# pocketbone.net
KiCad netlist of a schematic drawn in EAGLE
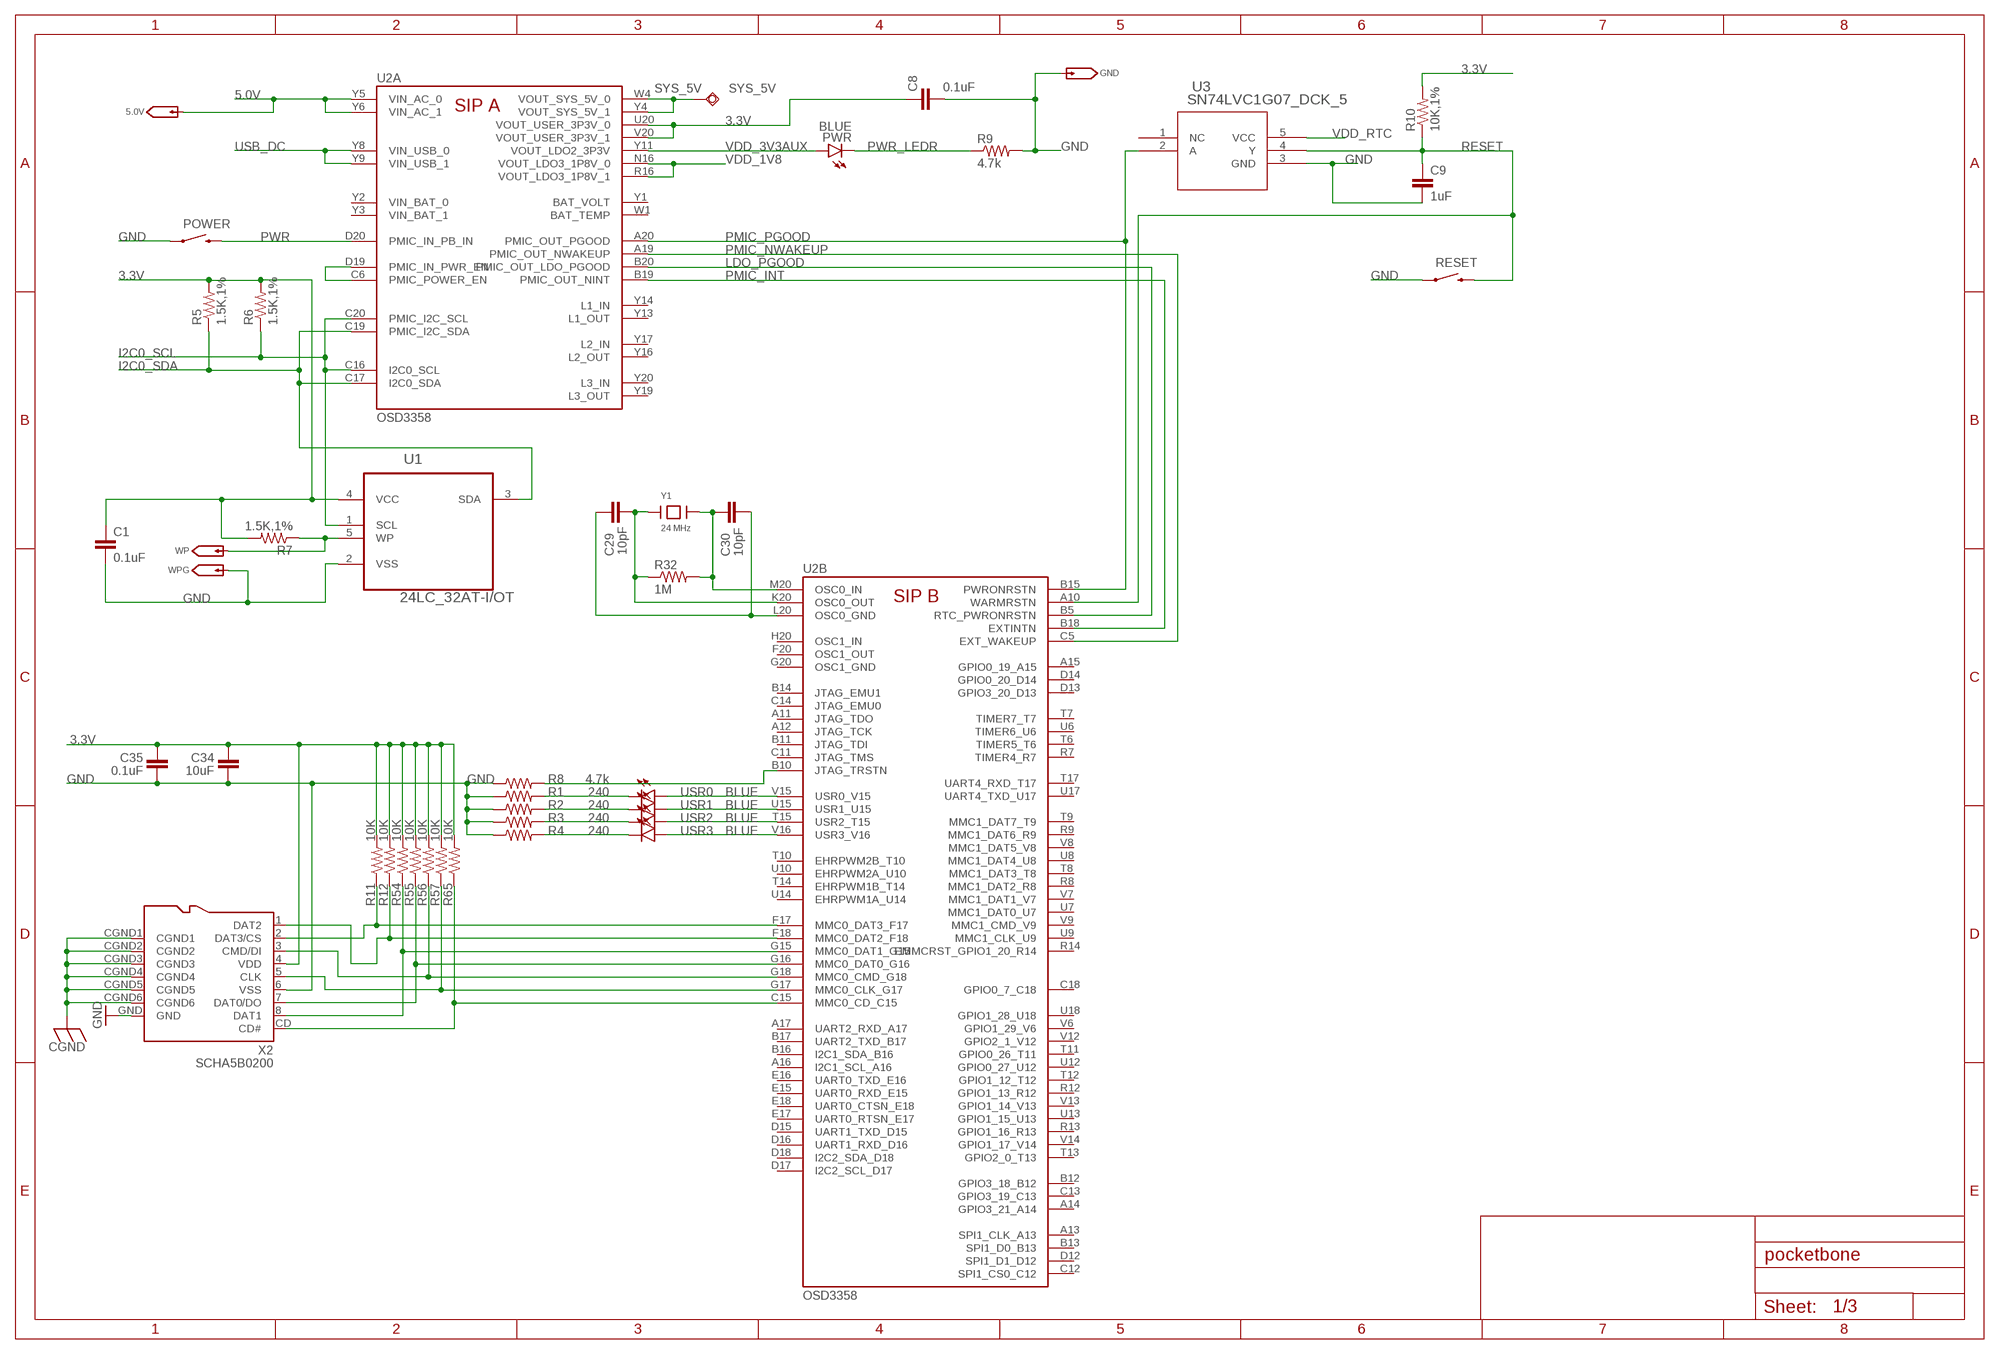
[diagram p0: schematic, sheet 1]
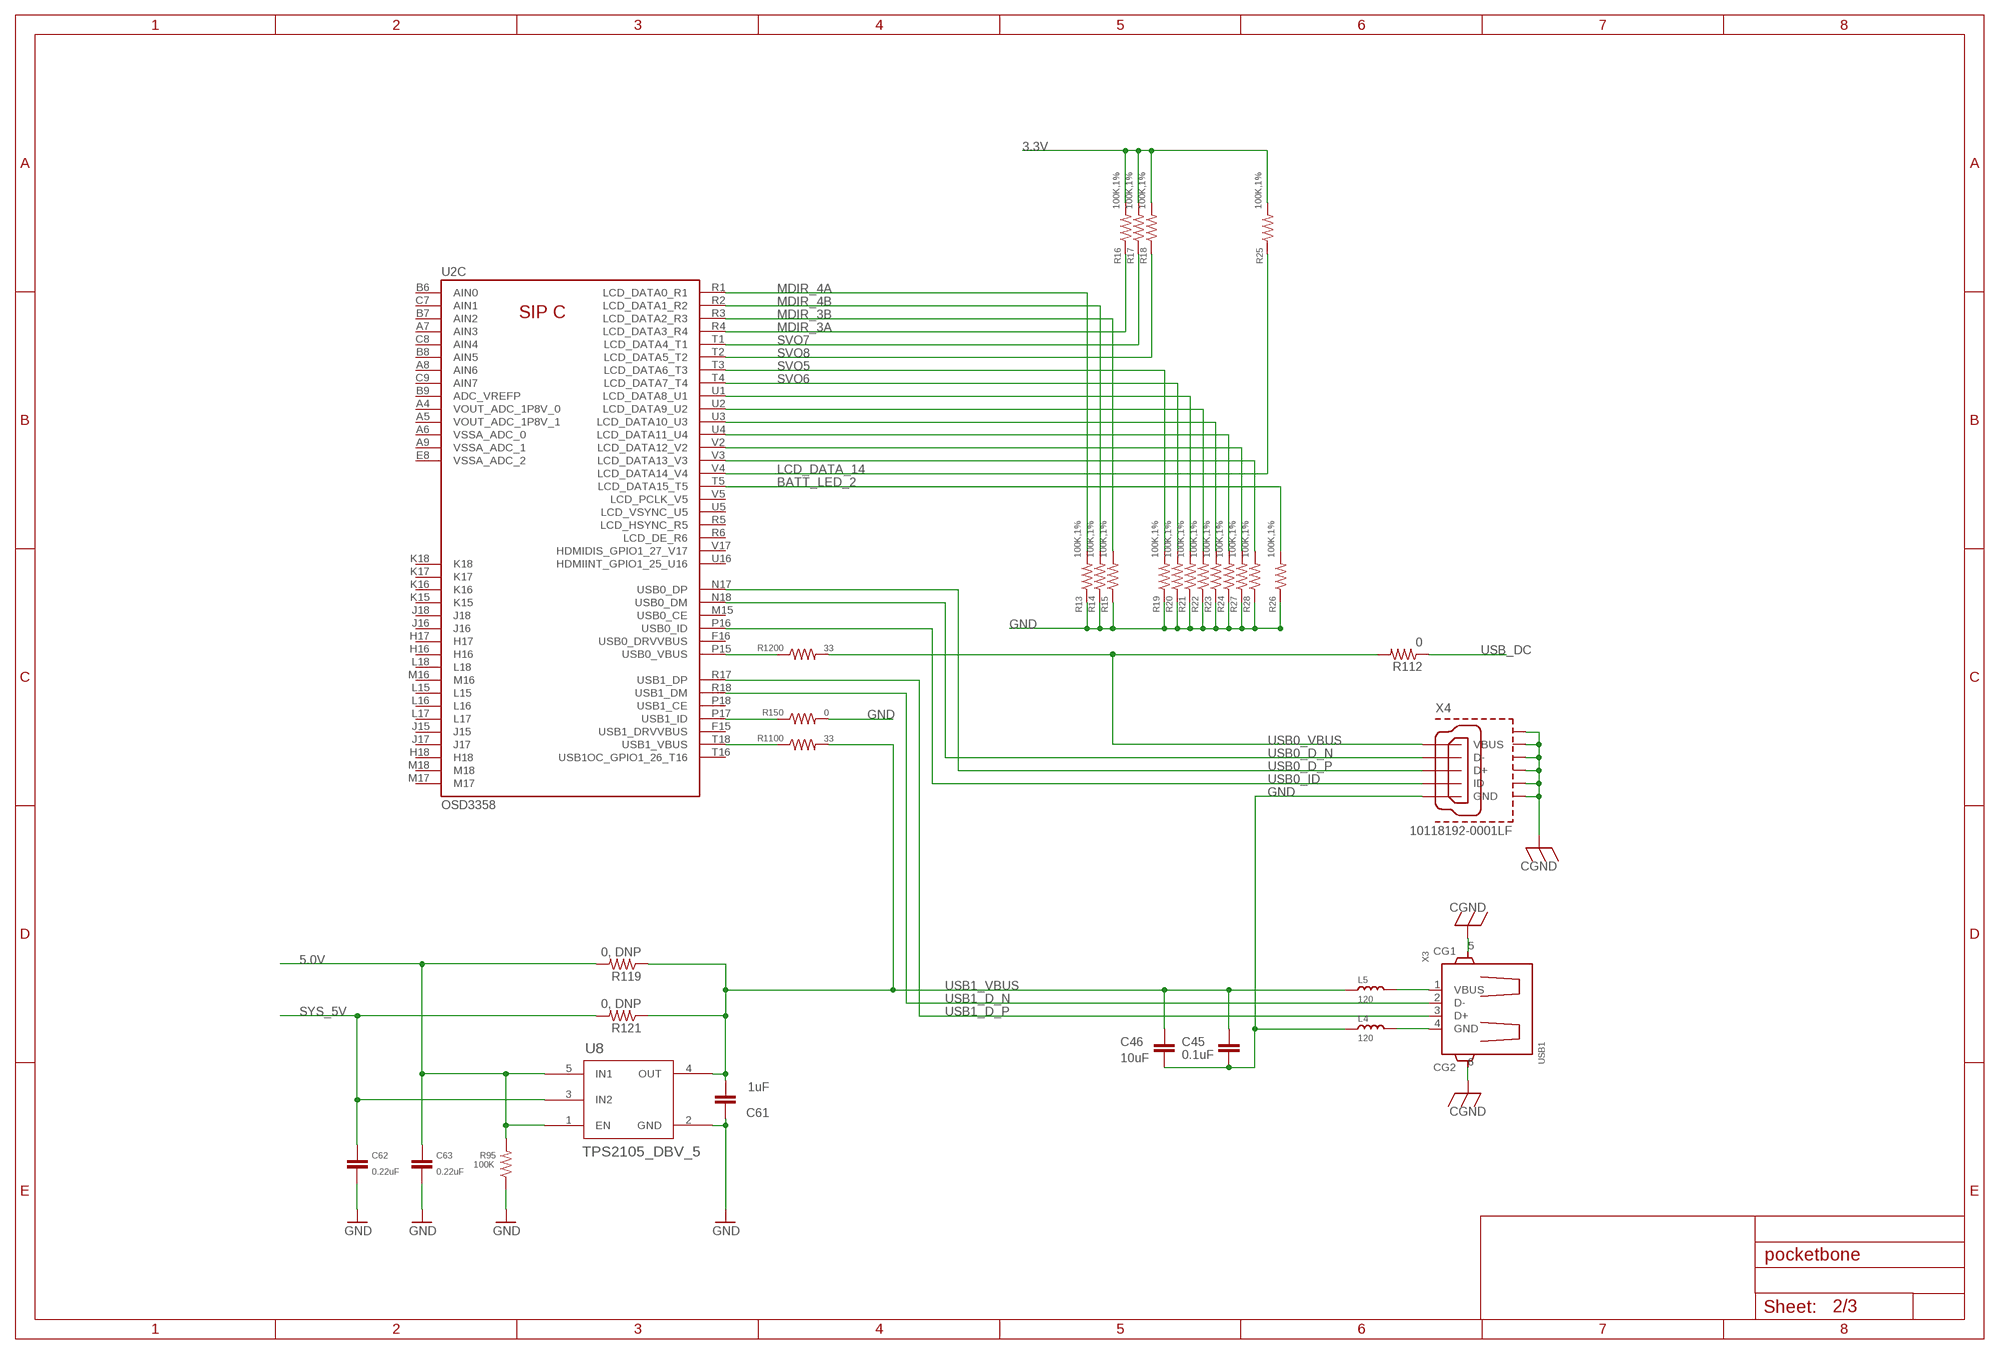
[diagram p1: schematic, sheet 2]
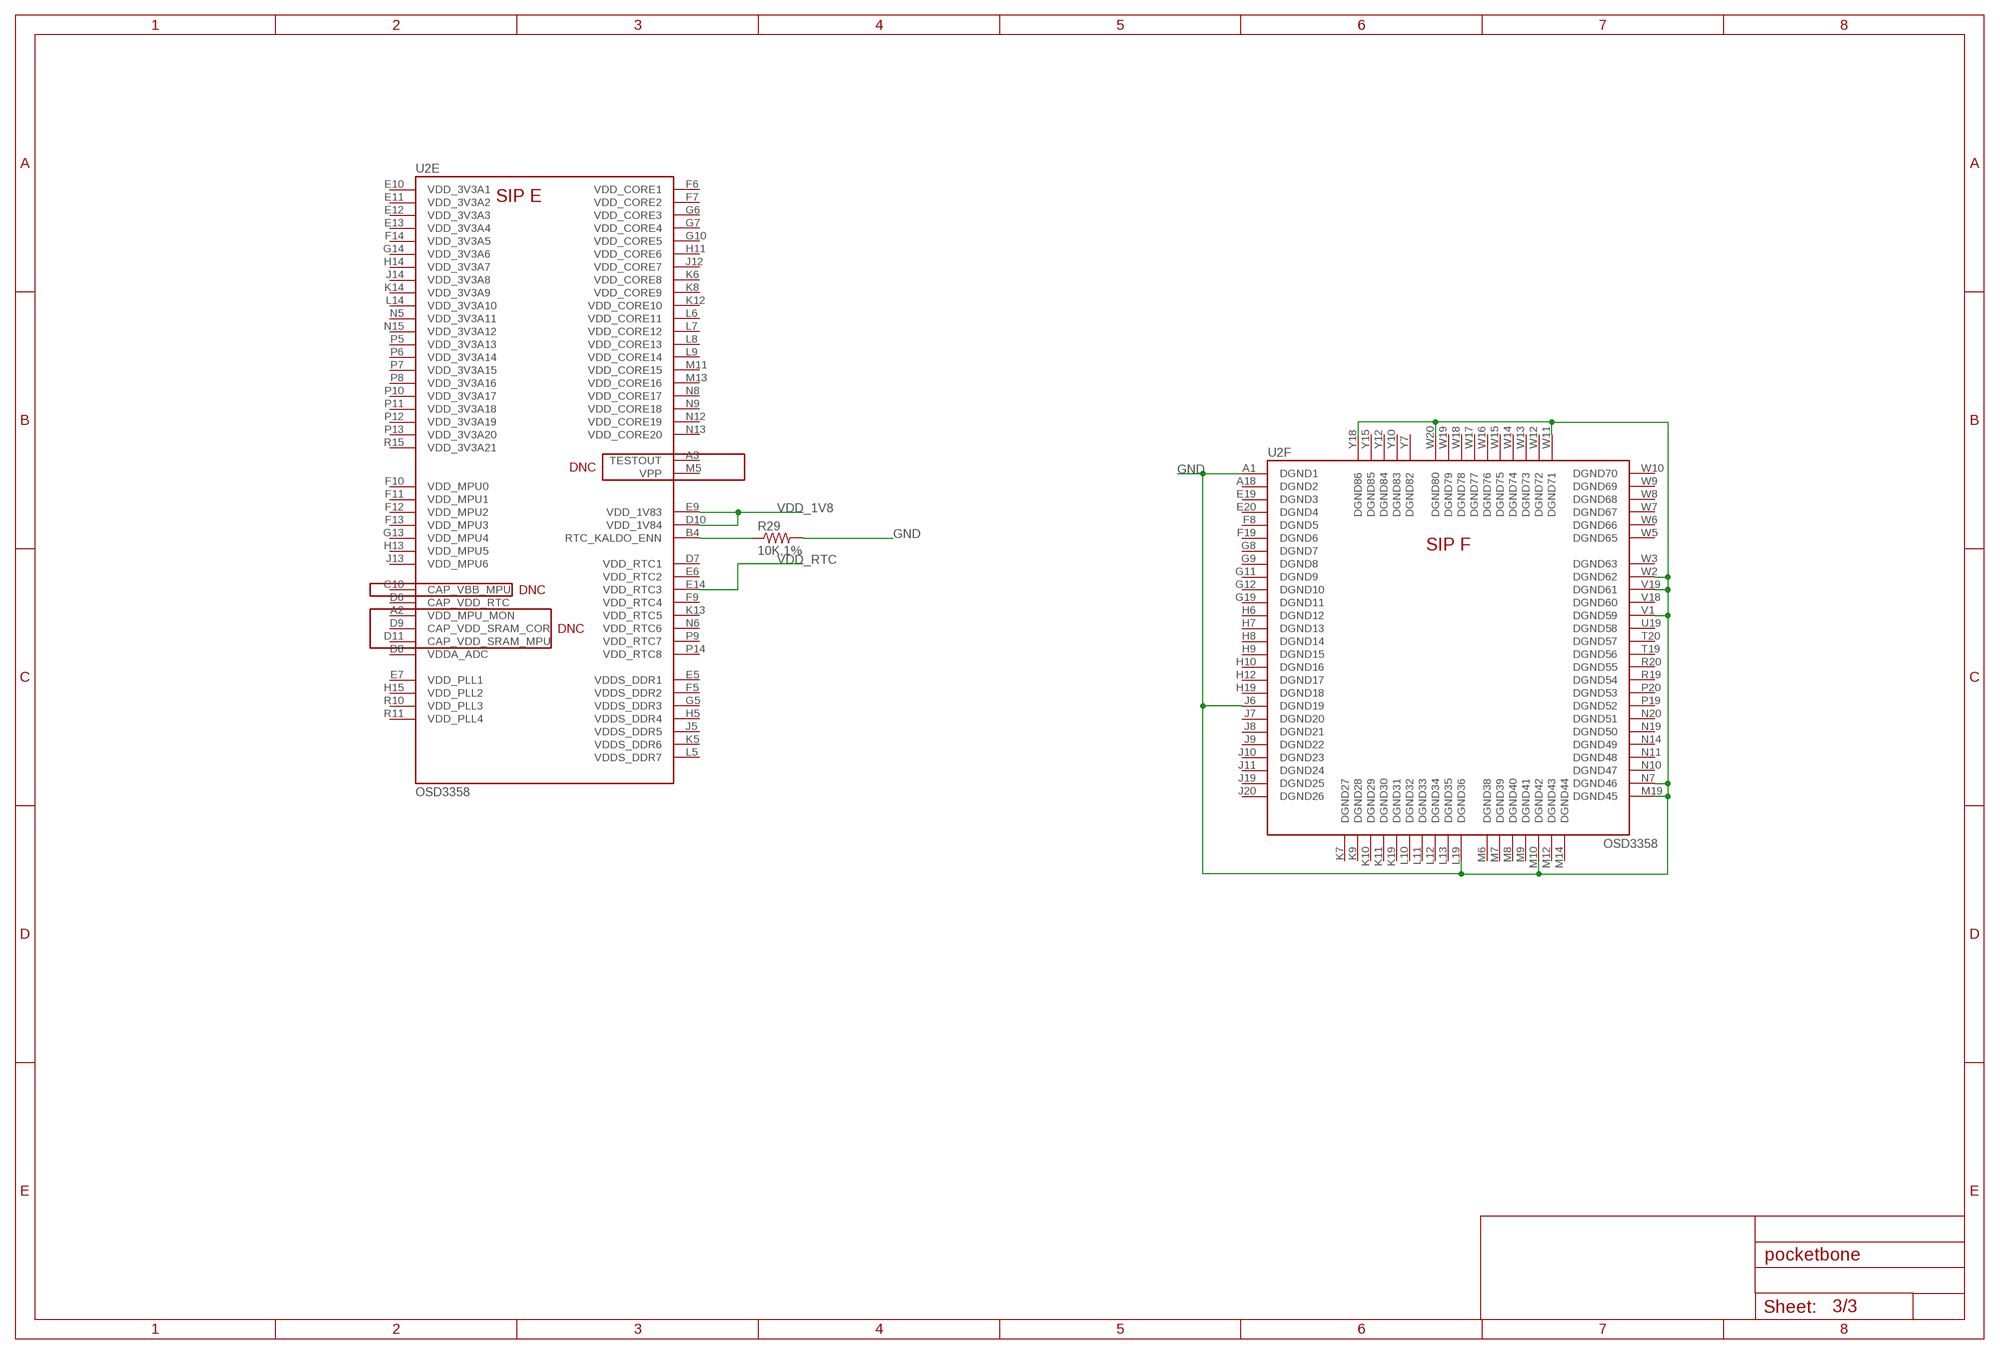
[diagram p2: schematic, sheet 3]

(export (version "E")
  (design (tool "Eeschema 10.0.6"))
  (components
    (comp (ref "C45")
      (value "0.1uF")
      (footprint "eagle-import:0402-CAP")
      (libsource (lib "eagle-import") (part "CAP0402-CAP"))
    )
    (comp (ref "C46")
      (value "10uF")
      (footprint "eagle-import:0805")
      (libsource (lib "eagle-import") (part "CAP0805"))
    )
    (comp (ref "C61")
      (value "1uF")
      (footprint "eagle-import:0402-CAP")
      (libsource (lib "eagle-import") (part "CAP0402-CAP"))
    )
    (comp (ref "C62")
      (value "0.22uF")
      (footprint "eagle-import:0402-CAP")
      (libsource (lib "eagle-import") (part "CAP0402-CAP"))
    )
    (comp (ref "C63")
      (value "0.22uF")
      (footprint "eagle-import:0402-CAP")
      (libsource (lib "eagle-import") (part "CAP0402-CAP"))
    )
    (comp (ref "L4")
      (value "120")
      (footprint "eagle-import:L0603")
      (libsource (lib "eagle-import") (part "INDUCTOR/FERRITE-BEAD'0603'"))
    )
    (comp (ref "L5")
      (value "120")
      (footprint "eagle-import:L0603")
      (libsource (lib "eagle-import") (part "INDUCTOR/FERRITE-BEAD'0603'"))
    )
    (comp (ref "R13")
      (value "100K,1%")
      (footprint "eagle-import:0402-RES")
      (libsource (lib "eagle-import") (part "RESISTOR0402-RES"))
    )
    (comp (ref "R14")
      (value "100K,1%")
      (footprint "eagle-import:0402-RES")
      (libsource (lib "eagle-import") (part "RESISTOR0402-RES"))
    )
    (comp (ref "R15")
      (value "100K,1%")
      (footprint "eagle-import:0402-RES")
      (libsource (lib "eagle-import") (part "RESISTOR0402-RES"))
    )
    (comp (ref "R16")
      (value "100K,1%")
      (footprint "eagle-import:0402-RES")
      (libsource (lib "eagle-import") (part "RESISTOR0402-RES"))
    )
    (comp (ref "R17")
      (value "100K,1%")
      (footprint "eagle-import:0402-RES")
      (libsource (lib "eagle-import") (part "RESISTOR0402-RES"))
    )
    (comp (ref "R18")
      (value "100K,1%")
      (footprint "eagle-import:0402-RES")
      (libsource (lib "eagle-import") (part "RESISTOR0402-RES"))
    )
    (comp (ref "R19")
      (value "100K,1%")
      (footprint "eagle-import:0402-RES")
      (libsource (lib "eagle-import") (part "RESISTOR0402-RES"))
    )
    (comp (ref "R20")
      (value "100K,1%")
      (footprint "eagle-import:0402-RES")
      (libsource (lib "eagle-import") (part "RESISTOR0402-RES"))
    )
    (comp (ref "R21")
      (value "100K,1%")
      (footprint "eagle-import:0402-RES")
      (libsource (lib "eagle-import") (part "RESISTOR0402-RES"))
    )
    (comp (ref "R22")
      (value "100K,1%")
      (footprint "eagle-import:0402-RES")
      (libsource (lib "eagle-import") (part "RESISTOR0402-RES"))
    )
    (comp (ref "R23")
      (value "100K,1%")
      (footprint "eagle-import:0402-RES")
      (libsource (lib "eagle-import") (part "RESISTOR0402-RES"))
    )
    (comp (ref "R24")
      (value "100K,1%")
      (footprint "eagle-import:0402-RES")
      (libsource (lib "eagle-import") (part "RESISTOR0402-RES"))
    )
    (comp (ref "R25")
      (value "100K,1%")
      (footprint "eagle-import:0402-RES")
      (libsource (lib "eagle-import") (part "RESISTOR0402-RES"))
    )
    (comp (ref "R26")
      (value "100K,1%")
      (footprint "eagle-import:0402-RES")
      (libsource (lib "eagle-import") (part "RESISTOR0402-RES"))
    )
    (comp (ref "R27")
      (value "100K,1%")
      (footprint "eagle-import:0402-RES")
      (libsource (lib "eagle-import") (part "RESISTOR0402-RES"))
    )
    (comp (ref "R28")
      (value "100K,1%")
      (footprint "eagle-import:0402-RES")
      (libsource (lib "eagle-import") (part "RESISTOR0402-RES"))
    )
    (comp (ref "R95")
      (value "100K")
      (footprint "eagle-import:0402-RES")
      (libsource (lib "eagle-import") (part "RESISTOR0402-RES"))
    )
    (comp (ref "R112")
      (value "0")
      (footprint "eagle-import:0603-RES")
      (libsource (lib "eagle-import") (part "RESISTOR0603"))
    )
    (comp (ref "R119")
      (value "0, DNP")
      (footprint "eagle-import:0603-RES")
      (libsource (lib "eagle-import") (part "RESISTOR0603"))
    )
    (comp (ref "R121")
      (value "0, DNP")
      (footprint "eagle-import:0603-RES")
      (libsource (lib "eagle-import") (part "RESISTOR0603"))
    )
    (comp (ref "R150")
      (value "0")
      (footprint "eagle-import:0402-RES")
      (libsource (lib "eagle-import") (part "RESISTOR0402-RES"))
    )
    (comp (ref "R1100")
      (value "33")
      (footprint "eagle-import:0402-RES")
      (libsource (lib "eagle-import") (part "RESISTOR0402-RES"))
    )
    (comp (ref "R1200")
      (value "33")
      (footprint "eagle-import:0402-RES")
      (libsource (lib "eagle-import") (part "RESISTOR0402-RES"))
    )
    (comp (ref "U2")
      (value "OSD3358")
      (footprint "eagle-import:OSD3358")
      (libsource (lib "eagle-import") (part "OSD3358"))
    )
    (comp (ref "U8")
      (value "TPS2105_DBV_5")
      (footprint "eagle-import:DBV5")
      (fields
        (field (name "GENERIC_PART_NUMBER") "TPS2105")
        (field (name "MANUFACTURER") "Texas Instruments")
        (field (name "MANUFACTURER_PART_NUMBER") "tps2105_dbv_5")
      )
      (libsource (lib "eagle-import") (part "TPS2105_DBV_5"))
    )
    (comp (ref "X3")
      (value "USB1")
      (footprint "eagle-import:USB_HOST_HORIZONTAL_W_CHASSIS_GND")
      (libsource (lib "eagle-import") (part "USB_HOST_W/CHASSIS_GND"))
    )
    (comp (ref "X4")
      (value "10118192-0001LF")
      (footprint "eagle-import:10118192-0001LF(MICRO-USB-B-AMPHENOL-FCI)")
      (libsource (lib "eagle-import") (part "10118192-0001LF"))
    )
    (comp (ref "5.0V")
      (value "GHI_TESTPAD/W_HOLE_1X1")
      (footprint "eagle-import:GHI2_TESTPAD_W_HOLE_1X1")
      (libsource (lib "eagle-import") (part "GHI_TESTPAD/W_HOLE_1X1"))
    )
    (comp (ref "C1")
      (value "0.1uF")
      (footprint "eagle-import:0402-CAP")
      (libsource (lib "eagle-import") (part "CAP0402-CAP"))
    )
    (comp (ref "C8")
      (value "0.1uF")
      (footprint "eagle-import:0402-CAP")
      (libsource (lib "eagle-import") (part "CAP0402-CAP"))
    )
    (comp (ref "C9")
      (value "1uF")
      (footprint "eagle-import:0402-CAP")
      (libsource (lib "eagle-import") (part "CAP0402-CAP"))
    )
    (comp (ref "C29")
      (value "10pF")
      (footprint "eagle-import:0402-CAP")
      (libsource (lib "eagle-import") (part "CAP0402-CAP"))
    )
    (comp (ref "C30")
      (value "10pF")
      (footprint "eagle-import:0402-CAP")
      (libsource (lib "eagle-import") (part "CAP0402-CAP"))
    )
    (comp (ref "C34")
      (value "10uF")
      (footprint "eagle-import:0805")
      (libsource (lib "eagle-import") (part "CAP0805"))
    )
    (comp (ref "C35")
      (value "0.1uF")
      (footprint "eagle-import:0402-CAP")
      (libsource (lib "eagle-import") (part "CAP0402-CAP"))
    )
    (comp (ref "GND")
      (value "GHI_TESTPAD/W_HOLE_1X1")
      (footprint "eagle-import:GHI2_TESTPAD_W_HOLE_1X1")
      (libsource (lib "eagle-import") (part "GHI_TESTPAD/W_HOLE_1X1"))
    )
    (comp (ref "POWER")
      (value "SWITCH-MOMENTARY-2SMD-1101NE")
      (footprint "eagle-import:TACTILE-SWITCH-1101NE")
      (libsource (lib "eagle-import") (part "SWITCH-MOMENTARY-2SMD-1101NE"))
    )
    (comp (ref "PWR")
      (value "BLUE")
      (footprint "eagle-import:LED-0603")
      (libsource (lib "eagle-import") (part "LED0603"))
    )
    (comp (ref "R1")
      (value "240")
      (footprint "eagle-import:0402-RES")
      (libsource (lib "eagle-import") (part "RESISTOR0402-RES"))
    )
    (comp (ref "R2")
      (value "240")
      (footprint "eagle-import:0402-RES")
      (libsource (lib "eagle-import") (part "RESISTOR0402-RES"))
    )
    (comp (ref "R3")
      (value "240")
      (footprint "eagle-import:0402-RES")
      (libsource (lib "eagle-import") (part "RESISTOR0402-RES"))
    )
    (comp (ref "R4")
      (value "240")
      (footprint "eagle-import:0402-RES")
      (libsource (lib "eagle-import") (part "RESISTOR0402-RES"))
    )
    (comp (ref "R5")
      (value "1.5K,1%")
      (footprint "eagle-import:0402-RES")
      (libsource (lib "eagle-import") (part "RESISTOR0402-RES"))
    )
    (comp (ref "R6")
      (value "1.5K,1%")
      (footprint "eagle-import:0402-RES")
      (libsource (lib "eagle-import") (part "RESISTOR0402-RES"))
    )
    (comp (ref "R7")
      (value "1.5K,1%")
      (footprint "eagle-import:0402-RES")
      (libsource (lib "eagle-import") (part "RESISTOR0402-RES"))
    )
    (comp (ref "R8")
      (value "4.7k")
      (footprint "eagle-import:0402-RES")
      (libsource (lib "eagle-import") (part "RESISTOR0402-RES"))
    )
    (comp (ref "R9")
      (value "4.7k")
      (footprint "eagle-import:0402-RES")
      (libsource (lib "eagle-import") (part "RESISTOR0402-RES"))
    )
    (comp (ref "R10")
      (value "10K,1%")
      (footprint "eagle-import:0402-RES")
      (libsource (lib "eagle-import") (part "RESISTOR0402-RES"))
    )
    (comp (ref "R11")
      (value "10K")
      (footprint "eagle-import:0402-RES")
      (libsource (lib "eagle-import") (part "RESISTOR0402-RES"))
    )
    (comp (ref "R12")
      (value "10K")
      (footprint "eagle-import:0402-RES")
      (libsource (lib "eagle-import") (part "RESISTOR0402-RES"))
    )
    (comp (ref "R32")
      (value "1M")
      (footprint "eagle-import:0402-RES")
      (libsource (lib "eagle-import") (part "RESISTOR0402-RES"))
    )
    (comp (ref "R54")
      (value "10K")
      (footprint "eagle-import:0402-RES")
      (libsource (lib "eagle-import") (part "RESISTOR0402-RES"))
    )
    (comp (ref "R55")
      (value "10K")
      (footprint "eagle-import:0402-RES")
      (libsource (lib "eagle-import") (part "RESISTOR0402-RES"))
    )
    (comp (ref "R56")
      (value "10K")
      (footprint "eagle-import:0402-RES")
      (libsource (lib "eagle-import") (part "RESISTOR0402-RES"))
    )
    (comp (ref "R57")
      (value "10K")
      (footprint "eagle-import:0402-RES")
      (libsource (lib "eagle-import") (part "RESISTOR0402-RES"))
    )
    (comp (ref "R65")
      (value "10K")
      (footprint "eagle-import:0402-RES")
      (libsource (lib "eagle-import") (part "RESISTOR0402-RES"))
    )
    (comp (ref "RESET")
      (value "SWITCH-MOMENTARY-2SMD-1101NE")
      (footprint "eagle-import:TACTILE-SWITCH-1101NE")
      (libsource (lib "eagle-import") (part "SWITCH-MOMENTARY-2SMD-1101NE"))
    )
    (comp (ref "SYS_5V")
      (value "TPSQB1,27")
      (footprint "eagle-import:B1,27")
      (libsource (lib "eagle-import") (part "TPSQB1,27"))
    )
    (comp (ref "U1")
      (value "24LC_32AT-I/OT")
      (footprint "eagle-import:SOT95P290X145-5N")
      (fields (field (name "MPN") "24LC32AT-I/OT"))
      (libsource (lib "eagle-import") (part "24LC_32AT-I/OT"))
    )
    (comp (ref "U3")
      (value "SN74LVC1G07_DCK_5")
      (footprint "eagle-import:DCK5")
      (fields
        (field (name "GENERIC_PART_NUMBER") "SN74LVC1G07")
        (field (name "MANUFACTURER") "Texas Instruments")
        (field (name "MANUFACTURER_PART_NUMBER") "sn74lvc1g07_dck_5")
      )
      (libsource (lib "eagle-import") (part "SN74LVC1G07_DCK_5"))
    )
    (comp (ref "USR0")
      (value "BLUE")
      (footprint "eagle-import:LED-0603")
      (libsource (lib "eagle-import") (part "LED0603"))
    )
    (comp (ref "USR1")
      (value "BLUE")
      (footprint "eagle-import:LED-0603")
      (libsource (lib "eagle-import") (part "LED0603"))
    )
    (comp (ref "USR2")
      (value "BLUE")
      (footprint "eagle-import:LED-0603")
      (libsource (lib "eagle-import") (part "LED0603"))
    )
    (comp (ref "USR3")
      (value "BLUE")
      (footprint "eagle-import:LED-0603")
      (libsource (lib "eagle-import") (part "LED0603"))
    )
    (comp (ref "WP")
      (value "GHI_TESTPAD/W_HOLE_1X1")
      (footprint "eagle-import:GHI2_TESTPAD_W_HOLE_1X1")
      (libsource (lib "eagle-import") (part "GHI_TESTPAD/W_HOLE_1X1"))
    )
    (comp (ref "WPG")
      (value "GHI_TESTPAD/W_HOLE_1X1")
      (footprint "eagle-import:GHI2_TESTPAD_W_HOLE_1X1")
      (libsource (lib "eagle-import") (part "GHI_TESTPAD/W_HOLE_1X1"))
    )
    (comp (ref "X2")
      (value "SCHA5B0200")
      (footprint "eagle-import:SCHA5B0200")
      (libsource (lib "eagle-import") (part "SCHA5B0200(ALPS_USD)"))
    )
    (comp (ref "Y1")
      (value "24 MHz")
      (footprint "eagle-import:CRYSTAL_5X3.2MM")
      (libsource (lib "eagle-import") (part "CRYSTAL_5X3.2MM"))
    )
    (comp (ref "R29")
      (value "10K,1%")
      (footprint "eagle-import:0402-RES")
      (libsource (lib "eagle-import") (part "RESISTOR0402-RES"))
    )
  )
  (nets
    (net (code "1") (name "3.3V") (class "Default")
      (node (ref "C1") (pin "1") (pinfunction "1_1") (pintype "passive"))
      (node (ref "C34") (pin "2") (pinfunction "2_2") (pintype "passive"))
      (node (ref "C35") (pin "2") (pinfunction "2_2") (pintype "passive"))
      (node (ref "C8") (pin "1") (pinfunction "1_1") (pintype "passive"))
      (node (ref "R10") (pin "2") (pinfunction "2_2") (pintype "passive"))
      (node (ref "R11") (pin "2") (pinfunction "2_2") (pintype "passive"))
      (node (ref "R12") (pin "2") (pinfunction "2_2") (pintype "passive"))
      (node (ref "R16") (pin "2") (pinfunction "2_2") (pintype "passive"))
      (node (ref "R17") (pin "2") (pinfunction "2_2") (pintype "passive"))
      (node (ref "R18") (pin "2") (pinfunction "2_2") (pintype "passive"))
      (node (ref "R25") (pin "2") (pinfunction "2_2") (pintype "passive"))
      (node (ref "R5") (pin "2") (pinfunction "2_2") (pintype "passive"))
      (node (ref "R54") (pin "2") (pinfunction "2_2") (pintype "passive"))
      (node (ref "R55") (pin "2") (pinfunction "2_2") (pintype "passive"))
      (node (ref "R56") (pin "2") (pinfunction "2_2") (pintype "passive"))
      (node (ref "R57") (pin "2") (pinfunction "2_2") (pintype "passive"))
      (node (ref "R6") (pin "2") (pinfunction "2_2") (pintype "passive"))
      (node (ref "R65") (pin "2") (pinfunction "2_2") (pintype "passive"))
      (node (ref "R7") (pin "2") (pinfunction "2_2") (pintype "passive"))
      (node (ref "U1") (pin "4") (pinfunction "VCC_4") (pintype "power_in"))
      (node (ref "U2") (pin "U20") (pinfunction "VOUT_USER_3P3V_0_U20") (pintype "power_in"))
      (node (ref "U2") (pin "V20") (pinfunction "VOUT_USER_3P3V_1_V20") (pintype "power_in"))
      (node (ref "X2") (pin "4") (pinfunction "VDD_4") (pintype "bidirectional"))
    )
    (net (code "2") (name "5.0V") (class "Default")
      (node (ref "5.0V") (pin "P$1") (pinfunction "TP_P$1") (pintype "bidirectional"))
      (node (ref "C63") (pin "1") (pinfunction "1_1") (pintype "passive"))
      (node (ref "R119") (pin "2") (pinfunction "2_2") (pintype "passive"))
      (node (ref "R95") (pin "2") (pinfunction "2_2") (pintype "passive"))
      (node (ref "U2") (pin "Y5") (pinfunction "VIN_AC_0_Y5") (pintype "power_in"))
      (node (ref "U2") (pin "Y6") (pinfunction "VIN_AC_1_Y6") (pintype "power_in"))
      (node (ref "U8") (pin "1") (pinfunction "EN_1") (pintype "input"))
      (node (ref "U8") (pin "5") (pinfunction "IN1_5") (pintype "input"))
    )
    (net (code "3") (name "BATT_LED_2") (class "Default")
      (node (ref "R26") (pin "2") (pinfunction "2_2") (pintype "passive"))
      (node (ref "U2") (pin "T5") (pinfunction "LCD_DATA15_T5_T5") (pintype "bidirectional"))
    )
    (net (code "4") (name "CGND") (class "Default")
      (node (ref "X2") (pin "CGND1") (pinfunction "CGND1_CGND1") (pintype "bidirectional"))
      (node (ref "X2") (pin "CGND2") (pinfunction "CGND2_CGND2") (pintype "bidirectional"))
      (node (ref "X2") (pin "CGND3") (pinfunction "CGND3_CGND3") (pintype "bidirectional"))
      (node (ref "X2") (pin "CGND4") (pinfunction "CGND4_CGND4") (pintype "bidirectional"))
      (node (ref "X2") (pin "CGND5") (pinfunction "CGND5_CGND5") (pintype "bidirectional"))
      (node (ref "X2") (pin "CGND6") (pinfunction "CGND6_CGND6") (pintype "bidirectional"))
      (node (ref "X3") (pin "5") (pinfunction "CG1_5") (pintype "bidirectional"))
      (node (ref "X3") (pin "6") (pinfunction "CG2_6") (pintype "bidirectional"))
      (node (ref "X4") (pin "CGND1") (pinfunction "SGND1_CGND1") (pintype "bidirectional"))
      (node (ref "X4") (pin "CGND2") (pinfunction "SGND2_CGND2") (pintype "bidirectional"))
      (node (ref "X4") (pin "CGND3") (pinfunction "SGND3_CGND3") (pintype "bidirectional"))
      (node (ref "X4") (pin "CGND4") (pinfunction "SGND4_CGND4") (pintype "bidirectional"))
      (node (ref "X4") (pin "CGND5") (pinfunction "SGND5_CGND5") (pintype "bidirectional"))
      (node (ref "X4") (pin "CGND6") (pinfunction "SGND6_CGND6") (pintype "bidirectional"))
    )
    (net (code "5") (name "GND") (class "Default")
      (node (ref "C1") (pin "2") (pinfunction "2_2") (pintype "passive"))
      (node (ref "C34") (pin "1") (pinfunction "1_1") (pintype "passive"))
      (node (ref "C35") (pin "1") (pinfunction "1_1") (pintype "passive"))
      (node (ref "C45") (pin "2") (pinfunction "2_2") (pintype "passive"))
      (node (ref "C46") (pin "2") (pinfunction "2_2") (pintype "passive"))
      (node (ref "C61") (pin "1") (pinfunction "1_1") (pintype "passive"))
      (node (ref "C62") (pin "2") (pinfunction "2_2") (pintype "passive"))
      (node (ref "C63") (pin "2") (pinfunction "2_2") (pintype "passive"))
      (node (ref "C8") (pin "2") (pinfunction "2_2") (pintype "passive"))
      (node (ref "C9") (pin "2") (pinfunction "2_2") (pintype "passive"))
      (node (ref "GND") (pin "P$1") (pinfunction "TP_P$1") (pintype "bidirectional"))
      (node (ref "L4") (pin "1") (pinfunction "1_1") (pintype "passive"))
      (node (ref "POWER") (pin "1") (pinfunction "1_1") (pintype "passive"))
      (node (ref "R1") (pin "1") (pinfunction "1_1") (pintype "passive"))
      (node (ref "R13") (pin "1") (pinfunction "1_1") (pintype "passive"))
      (node (ref "R14") (pin "1") (pinfunction "1_1") (pintype "passive"))
      (node (ref "R15") (pin "1") (pinfunction "1_1") (pintype "passive"))
      (node (ref "R150") (pin "2") (pinfunction "2_2") (pintype "passive"))
      (node (ref "R19") (pin "1") (pinfunction "1_1") (pintype "passive"))
      (node (ref "R2") (pin "1") (pinfunction "1_1") (pintype "passive"))
      (node (ref "R20") (pin "1") (pinfunction "1_1") (pintype "passive"))
      (node (ref "R21") (pin "1") (pinfunction "1_1") (pintype "passive"))
      (node (ref "R22") (pin "1") (pinfunction "1_1") (pintype "passive"))
      (node (ref "R23") (pin "1") (pinfunction "1_1") (pintype "passive"))
      (node (ref "R24") (pin "1") (pinfunction "1_1") (pintype "passive"))
      (node (ref "R26") (pin "1") (pinfunction "1_1") (pintype "passive"))
      (node (ref "R27") (pin "1") (pinfunction "1_1") (pintype "passive"))
      (node (ref "R28") (pin "1") (pinfunction "1_1") (pintype "passive"))
      (node (ref "R29") (pin "2") (pinfunction "2_2") (pintype "passive"))
      (node (ref "R3") (pin "1") (pinfunction "1_1") (pintype "passive"))
      (node (ref "R4") (pin "1") (pinfunction "1_1") (pintype "passive"))
      (node (ref "R8") (pin "1") (pinfunction "1_1") (pintype "passive"))
      (node (ref "R9") (pin "2") (pinfunction "2_2") (pintype "passive"))
      (node (ref "R95") (pin "1") (pinfunction "1_1") (pintype "passive"))
      (node (ref "RESET") (pin "1") (pinfunction "1_1") (pintype "passive"))
      (node (ref "U1") (pin "2") (pinfunction "VSS_2") (pintype "passive"))
      (node (ref "U2") (pin "A1") (pinfunction "DGND1_A1") (pintype "bidirectional"))
      (node (ref "U2") (pin "J6") (pinfunction "DGND19_J6") (pintype "bidirectional"))
      (node (ref "U2") (pin "L19") (pinfunction "DGND36_L19") (pintype "bidirectional"))
      (node (ref "U2") (pin "M10") (pinfunction "DGND42_M10") (pintype "bidirectional"))
      (node (ref "U2") (pin "M19") (pinfunction "DGND45_M19") (pintype "bidirectional"))
      (node (ref "U2") (pin "N7") (pinfunction "DGND46_N7") (pintype "bidirectional"))
      (node (ref "U2") (pin "V1") (pinfunction "DGND59_V1") (pintype "bidirectional"))
      (node (ref "U2") (pin "V19") (pinfunction "DGND61_V19") (pintype "bidirectional"))
      (node (ref "U2") (pin "W11") (pinfunction "DGND71_W11") (pintype "bidirectional"))
      (node (ref "U2") (pin "W2") (pinfunction "DGND62_W2") (pintype "bidirectional"))
      (node (ref "U2") (pin "W20") (pinfunction "DGND80_W20") (pintype "bidirectional"))
      (node (ref "U2") (pin "Y18") (pinfunction "DGND86_Y18") (pintype "bidirectional"))
      (node (ref "U3") (pin "3") (pinfunction "GND_3") (pintype "power_in"))
      (node (ref "U8") (pin "2") (pinfunction "GND_2") (pintype "power_in"))
      (node (ref "WPG") (pin "P$1") (pinfunction "TP_P$1") (pintype "bidirectional"))
      (node (ref "X2") (pin "6") (pinfunction "VSS_6") (pintype "bidirectional"))
      (node (ref "X2") (pin "GND") (pinfunction "GND_GND") (pintype "bidirectional"))
      (node (ref "X4") (pin "GND") (pinfunction "GND_GND") (pintype "input"))
    )
    (net (code "6") (name "I2C0_SCL") (class "Default")
      (node (ref "R6") (pin "1") (pinfunction "1_1") (pintype "passive"))
      (node (ref "U1") (pin "1") (pinfunction "SCL_1") (pintype "input"))
      (node (ref "U2") (pin "C16") (pinfunction "I2C0_SCL_C16") (pintype "bidirectional"))
      (node (ref "U2") (pin "C20") (pinfunction "PMIC_I2C_SCL_C20") (pintype "bidirectional"))
    )
    (net (code "7") (name "I2C0_SDA") (class "Default")
      (node (ref "R5") (pin "1") (pinfunction "1_1") (pintype "passive"))
      (node (ref "U1") (pin "3") (pinfunction "SDA_3") (pintype "bidirectional"))
      (node (ref "U2") (pin "C17") (pinfunction "I2C0_SDA_C17") (pintype "bidirectional"))
      (node (ref "U2") (pin "C19") (pinfunction "PMIC_I2C_SDA_C19") (pintype "bidirectional"))
    )
    (net (code "8") (name "LCD_DATA_14") (class "Default")
      (node (ref "R25") (pin "1") (pinfunction "1_1") (pintype "passive"))
      (node (ref "U2") (pin "V4") (pinfunction "LCD_DATA14_V4_V4") (pintype "bidirectional"))
    )
    (net (code "9") (name "LDO_PGOOD") (class "Default")
      (node (ref "U2") (pin "B20") (pinfunction "PMIC_OUT_LDO_PGOOD_B20") (pintype "output"))
      (node (ref "U2") (pin "B5") (pinfunction "RTC_PWRONRSTN_B5") (pintype "bidirectional"))
    )
    (net (code "10") (name "MDIR_3A") (class "Default")
      (node (ref "R16") (pin "1") (pinfunction "1_1") (pintype "passive"))
      (node (ref "U2") (pin "R4") (pinfunction "LCD_DATA3_R4_R4") (pintype "bidirectional"))
    )
    (net (code "11") (name "MDIR_3B") (class "Default")
      (node (ref "R15") (pin "2") (pinfunction "2_2") (pintype "passive"))
      (node (ref "U2") (pin "R3") (pinfunction "LCD_DATA2_R3_R3") (pintype "bidirectional"))
    )
    (net (code "12") (name "MDIR_4A") (class "Default")
      (node (ref "R13") (pin "2") (pinfunction "2_2") (pintype "passive"))
      (node (ref "U2") (pin "R1") (pinfunction "LCD_DATA0_R1_R1") (pintype "bidirectional"))
    )
    (net (code "13") (name "MDIR_4B") (class "Default")
      (node (ref "R14") (pin "2") (pinfunction "2_2") (pintype "passive"))
      (node (ref "U2") (pin "R2") (pinfunction "LCD_DATA1_R2_R2") (pintype "bidirectional"))
    )
    (net (code "14") (name "Net-(R1-Pad2)") (class "Default")
      (node (ref "R1") (pin "2") (pinfunction "2_2") (pintype "passive"))
      (node (ref "USR0") (pin "C") (pinfunction "C_C") (pintype "passive"))
    )
    (net (code "15") (name "Net-(R2-Pad2)") (class "Default")
      (node (ref "R2") (pin "2") (pinfunction "2_2") (pintype "passive"))
      (node (ref "USR1") (pin "C") (pinfunction "C_C") (pintype "passive"))
    )
    (net (code "16") (name "Net-(R3-Pad2)") (class "Default")
      (node (ref "R3") (pin "2") (pinfunction "2_2") (pintype "passive"))
      (node (ref "USR2") (pin "C") (pinfunction "C_C") (pintype "passive"))
    )
    (net (code "17") (name "Net-(R4-Pad2)") (class "Default")
      (node (ref "R4") (pin "2") (pinfunction "2_2") (pintype "passive"))
      (node (ref "USR3") (pin "C") (pinfunction "C_C") (pintype "passive"))
    )
    (net (code "18") (name "Net-(U1-WP)") (class "Default")
      (node (ref "R7") (pin "1") (pinfunction "1_1") (pintype "passive"))
      (node (ref "U1") (pin "5") (pinfunction "WP_5") (pintype "input"))
      (node (ref "WP") (pin "P$1") (pinfunction "TP_P$1") (pintype "bidirectional"))
    )
    (net (code "19") (name "Net-(U2A-PMIC_IN_PWR_EN)") (class "Default")
      (node (ref "U2") (pin "C6") (pinfunction "PMIC_POWER_EN_C6") (pintype "output"))
      (node (ref "U2") (pin "D19") (pinfunction "PMIC_IN_PWR_EN_D19") (pintype "input"))
    )
    (net (code "20") (name "Net-(U2B-JTAG_TRSTN)") (class "Default")
      (node (ref "R8") (pin "2") (pinfunction "2_2") (pintype "passive"))
      (node (ref "U2") (pin "B10") (pinfunction "JTAG_TRSTN_B10") (pintype "bidirectional"))
    )
    (net (code "21") (name "Net-(U2B-MMC0_CD_C15)") (class "Default")
      (node (ref "R65") (pin "1") (pinfunction "1_1") (pintype "passive"))
      (node (ref "U2") (pin "C15") (pinfunction "MMC0_CD_C15_C15") (pintype "bidirectional"))
      (node (ref "X2") (pin "CD") (pinfunction "CD#_CD") (pintype "bidirectional"))
    )
    (net (code "22") (name "Net-(U2B-MMC0_CLK_G17)") (class "Default")
      (node (ref "R57") (pin "1") (pinfunction "1_1") (pintype "passive"))
      (node (ref "U2") (pin "G17") (pinfunction "MMC0_CLK_G17_G17") (pintype "bidirectional"))
      (node (ref "X2") (pin "5") (pinfunction "CLK_5") (pintype "bidirectional"))
    )
    (net (code "23") (name "Net-(U2B-MMC0_CMD_G18)") (class "Default")
      (node (ref "R56") (pin "1") (pinfunction "1_1") (pintype "passive"))
      (node (ref "U2") (pin "G18") (pinfunction "MMC0_CMD_G18_G18") (pintype "bidirectional"))
      (node (ref "X2") (pin "3") (pinfunction "CMD/DI_3") (pintype "bidirectional"))
    )
    (net (code "24") (name "Net-(U2B-MMC0_DAT0_G16)") (class "Default")
      (node (ref "R55") (pin "1") (pinfunction "1_1") (pintype "passive"))
      (node (ref "U2") (pin "G16") (pinfunction "MMC0_DAT0_G16_G16") (pintype "bidirectional"))
      (node (ref "X2") (pin "7") (pinfunction "DAT0/DO_7") (pintype "bidirectional"))
    )
    (net (code "25") (name "Net-(U2B-MMC0_DAT1_G15)") (class "Default")
      (node (ref "R54") (pin "1") (pinfunction "1_1") (pintype "passive"))
      (node (ref "U2") (pin "G15") (pinfunction "MMC0_DAT1_G15_G15") (pintype "bidirectional"))
      (node (ref "X2") (pin "8") (pinfunction "DAT1_8") (pintype "bidirectional"))
    )
    (net (code "26") (name "Net-(U2B-MMC0_DAT2_F18)") (class "Default")
      (node (ref "R12") (pin "1") (pinfunction "1_1") (pintype "passive"))
      (node (ref "U2") (pin "F18") (pinfunction "MMC0_DAT2_F18_F18") (pintype "bidirectional"))
      (node (ref "X2") (pin "1") (pinfunction "DAT2_1") (pintype "bidirectional"))
    )
    (net (code "27") (name "Net-(U2B-MMC0_DAT3_F17)") (class "Default")
      (node (ref "R11") (pin "1") (pinfunction "1_1") (pintype "passive"))
      (node (ref "U2") (pin "F17") (pinfunction "MMC0_DAT3_F17_F17") (pintype "bidirectional"))
      (node (ref "X2") (pin "2") (pinfunction "DAT3/CS_2") (pintype "bidirectional"))
    )
    (net (code "28") (name "Net-(U2B-OSC0_GND)") (class "Default")
      (node (ref "C29") (pin "2") (pinfunction "2_2") (pintype "passive"))
      (node (ref "C30") (pin "2") (pinfunction "2_2") (pintype "passive"))
      (node (ref "U2") (pin "L20") (pinfunction "OSC0_GND_L20") (pintype "bidirectional"))
    )
    (net (code "29") (name "Net-(U2B-OSC0_IN)") (class "Default")
      (node (ref "C30") (pin "1") (pinfunction "1_1") (pintype "passive"))
      (node (ref "R32") (pin "2") (pinfunction "2_2") (pintype "passive"))
      (node (ref "U2") (pin "M20") (pinfunction "OSC0_IN_M20") (pintype "bidirectional"))
      (node (ref "Y1") (pin "2") (pinfunction "P$2_2") (pintype "passive"))
    )
    (net (code "30") (name "Net-(U2B-OSC0_OUT)") (class "Default")
      (node (ref "C29") (pin "1") (pinfunction "1_1") (pintype "passive"))
      (node (ref "R32") (pin "1") (pinfunction "1_1") (pintype "passive"))
      (node (ref "U2") (pin "K20") (pinfunction "OSC0_OUT_K20") (pintype "bidirectional"))
      (node (ref "Y1") (pin "1") (pinfunction "P$1_1") (pintype "passive"))
    )
    (net (code "31") (name "Net-(U2B-USR0_V15)") (class "Default")
      (node (ref "U2") (pin "V15") (pinfunction "USR0_V15_V15") (pintype "bidirectional"))
      (node (ref "USR0") (pin "A") (pinfunction "A_A") (pintype "passive"))
    )
    (net (code "32") (name "Net-(U2B-USR1_U15)") (class "Default")
      (node (ref "U2") (pin "U15") (pinfunction "USR1_U15_U15") (pintype "bidirectional"))
      (node (ref "USR1") (pin "A") (pinfunction "A_A") (pintype "passive"))
    )
    (net (code "33") (name "Net-(U2B-USR2_T15)") (class "Default")
      (node (ref "U2") (pin "T15") (pinfunction "USR2_T15_T15") (pintype "bidirectional"))
      (node (ref "USR2") (pin "A") (pinfunction "A_A") (pintype "passive"))
    )
    (net (code "34") (name "Net-(U2B-USR3_V16)") (class "Default")
      (node (ref "U2") (pin "V16") (pinfunction "USR3_V16_V16") (pintype "bidirectional"))
      (node (ref "USR3") (pin "A") (pinfunction "A_A") (pintype "passive"))
    )
    (net (code "35") (name "Net-(U2C-LCD_DATA8_U1)") (class "Default")
      (node (ref "R21") (pin "2") (pinfunction "2_2") (pintype "passive"))
      (node (ref "U2") (pin "U1") (pinfunction "LCD_DATA8_U1_U1") (pintype "bidirectional"))
    )
    (net (code "36") (name "Net-(U2C-LCD_DATA9_U2)") (class "Default")
      (node (ref "R22") (pin "2") (pinfunction "2_2") (pintype "passive"))
      (node (ref "U2") (pin "U2") (pinfunction "LCD_DATA9_U2_U2") (pintype "bidirectional"))
    )
    (net (code "37") (name "Net-(U2C-LCD_DATA10_U3)") (class "Default")
      (node (ref "R23") (pin "2") (pinfunction "2_2") (pintype "passive"))
      (node (ref "U2") (pin "U3") (pinfunction "LCD_DATA10_U3_U3") (pintype "bidirectional"))
    )
    (net (code "38") (name "Net-(U2C-LCD_DATA11_U4)") (class "Default")
      (node (ref "R24") (pin "2") (pinfunction "2_2") (pintype "passive"))
      (node (ref "U2") (pin "U4") (pinfunction "LCD_DATA11_U4_U4") (pintype "bidirectional"))
    )
    (net (code "39") (name "Net-(U2C-LCD_DATA12_V2)") (class "Default")
      (node (ref "R27") (pin "2") (pinfunction "2_2") (pintype "passive"))
      (node (ref "U2") (pin "V2") (pinfunction "LCD_DATA12_V2_V2") (pintype "bidirectional"))
    )
    (net (code "40") (name "Net-(U2C-LCD_DATA13_V3)") (class "Default")
      (node (ref "R28") (pin "2") (pinfunction "2_2") (pintype "passive"))
      (node (ref "U2") (pin "V3") (pinfunction "LCD_DATA13_V3_V3") (pintype "bidirectional"))
    )
    (net (code "41") (name "Net-(U2C-USB0_VBUS)") (class "Default")
      (node (ref "R1200") (pin "1") (pinfunction "1_1") (pintype "passive"))
      (node (ref "U2") (pin "P15") (pinfunction "USB0_VBUS_P15") (pintype "bidirectional"))
    )
    (net (code "42") (name "Net-(U2C-USB1_ID)") (class "Default")
      (node (ref "R150") (pin "1") (pinfunction "1_1") (pintype "passive"))
      (node (ref "U2") (pin "P17") (pinfunction "USB1_ID_P17") (pintype "bidirectional"))
    )
    (net (code "43") (name "Net-(U2C-USB1_VBUS)") (class "Default")
      (node (ref "R1100") (pin "1") (pinfunction "1_1") (pintype "passive"))
      (node (ref "U2") (pin "T18") (pinfunction "USB1_VBUS_T18") (pintype "bidirectional"))
    )
    (net (code "44") (name "Net-(U2E-RTC_KALDO_ENN)") (class "Default")
      (node (ref "R29") (pin "1") (pinfunction "1_1") (pintype "passive"))
      (node (ref "U2") (pin "B4") (pinfunction "RTC_KALDO_ENN_B4") (pintype "bidirectional"))
    )
    (net (code "45") (name "Net-(X3-GND)") (class "Default")
      (node (ref "L4") (pin "2") (pinfunction "2_2") (pintype "passive"))
      (node (ref "X3") (pin "4") (pinfunction "GND_4") (pintype "bidirectional"))
    )
    (net (code "46") (name "Net-(X3-VBUS)") (class "Default")
      (node (ref "L5") (pin "2") (pinfunction "2_2") (pintype "passive"))
      (node (ref "X3") (pin "1") (pinfunction "VBUS_1") (pintype "bidirectional"))
    )
    (net (code "47") (name "PMIC_INT") (class "Default")
      (node (ref "U2") (pin "B18") (pinfunction "EXTINTN_B18") (pintype "bidirectional"))
      (node (ref "U2") (pin "B19") (pinfunction "PMIC_OUT_NINT_B19") (pintype "output"))
    )
    (net (code "48") (name "PMIC_NWAKEUP") (class "Default")
      (node (ref "U2") (pin "A19") (pinfunction "PMIC_OUT_NWAKEUP_A19") (pintype "output"))
      (node (ref "U2") (pin "C5") (pinfunction "EXT_WAKEUP_C5") (pintype "bidirectional"))
    )
    (net (code "49") (name "PMIC_PGOOD") (class "Default")
      (node (ref "U2") (pin "A20") (pinfunction "PMIC_OUT_PGOOD_A20") (pintype "output"))
      (node (ref "U2") (pin "B15") (pinfunction "PWRONRSTN_B15") (pintype "bidirectional"))
      (node (ref "U3") (pin "2") (pinfunction "A_2") (pintype "input"))
    )
    (net (code "50") (name "PWR") (class "Default")
      (node (ref "POWER") (pin "2") (pinfunction "2_2") (pintype "passive"))
      (node (ref "U2") (pin "D20") (pinfunction "PMIC_IN_PB_IN_D20") (pintype "bidirectional"))
    )
    (net (code "51") (name "PWR_LEDR") (class "Default")
      (node (ref "PWR") (pin "C") (pinfunction "C_C") (pintype "passive"))
      (node (ref "R9") (pin "1") (pinfunction "1_1") (pintype "passive"))
    )
    (net (code "52") (name "RESET") (class "Default")
      (node (ref "C9") (pin "1") (pinfunction "1_1") (pintype "passive"))
      (node (ref "R10") (pin "1") (pinfunction "1_1") (pintype "passive"))
      (node (ref "RESET") (pin "2") (pinfunction "2_2") (pintype "passive"))
      (node (ref "U2") (pin "A10") (pinfunction "WARMRSTN_A10") (pintype "bidirectional"))
      (node (ref "U3") (pin "4") (pinfunction "Y_4") (pintype "output"))
    )
    (net (code "53") (name "SVO5") (class "Default")
      (node (ref "R19") (pin "2") (pinfunction "2_2") (pintype "passive"))
      (node (ref "U2") (pin "T3") (pinfunction "LCD_DATA6_T3_T3") (pintype "bidirectional"))
    )
    (net (code "54") (name "SVO6") (class "Default")
      (node (ref "R20") (pin "2") (pinfunction "2_2") (pintype "passive"))
      (node (ref "U2") (pin "T4") (pinfunction "LCD_DATA7_T4_T4") (pintype "bidirectional"))
    )
    (net (code "55") (name "SVO7") (class "Default")
      (node (ref "R17") (pin "1") (pinfunction "1_1") (pintype "passive"))
      (node (ref "U2") (pin "T1") (pinfunction "LCD_DATA4_T1_T1") (pintype "bidirectional"))
    )
    (net (code "56") (name "SVO8") (class "Default")
      (node (ref "R18") (pin "1") (pinfunction "1_1") (pintype "passive"))
      (node (ref "U2") (pin "T2") (pinfunction "LCD_DATA5_T2_T2") (pintype "bidirectional"))
    )
    (net (code "57") (name "SYS_5V") (class "Default")
      (node (ref "C62") (pin "1") (pinfunction "1_1") (pintype "passive"))
      (node (ref "R121") (pin "2") (pinfunction "2_2") (pintype "passive"))
      (node (ref "SYS_5V") (pin "TP") (pinfunction "TP_TP") (pintype "input"))
      (node (ref "U2") (pin "W4") (pinfunction "VOUT_SYS_5V_0_W4") (pintype "power_in"))
      (node (ref "U2") (pin "Y4") (pinfunction "VOUT_SYS_5V_1_Y4") (pintype "power_in"))
      (node (ref "U8") (pin "3") (pinfunction "IN2_3") (pintype "input"))
    )
    (net (code "58") (name "USB0_D_N") (class "Default")
      (node (ref "U2") (pin "N18") (pinfunction "USB0_DM_N18") (pintype "bidirectional"))
      (node (ref "X4") (pin "D-") (pinfunction "D-_D-") (pintype "input"))
    )
    (net (code "59") (name "USB0_D_P") (class "Default")
      (node (ref "U2") (pin "N17") (pinfunction "USB0_DP_N17") (pintype "bidirectional"))
      (node (ref "X4") (pin "D+") (pinfunction "D+_D+") (pintype "input"))
    )
    (net (code "60") (name "USB0_ID") (class "Default")
      (node (ref "U2") (pin "P16") (pinfunction "USB0_ID_P16") (pintype "bidirectional"))
      (node (ref "X4") (pin "ID") (pinfunction "ID_ID") (pintype "input"))
    )
    (net (code "61") (name "USB0_VBUS") (class "Default")
      (node (ref "R112") (pin "2") (pinfunction "2_2") (pintype "passive"))
      (node (ref "R1200") (pin "2") (pinfunction "2_2") (pintype "passive"))
      (node (ref "X4") (pin "VBUS") (pinfunction "VBUS_VBUS") (pintype "input"))
    )
    (net (code "62") (name "USB1_D_N") (class "Default")
      (node (ref "U2") (pin "R18") (pinfunction "USB1_DM_R18") (pintype "bidirectional"))
      (node (ref "X3") (pin "2") (pinfunction "D-_2") (pintype "bidirectional"))
    )
    (net (code "63") (name "USB1_D_P") (class "Default")
      (node (ref "U2") (pin "R17") (pinfunction "USB1_DP_R17") (pintype "bidirectional"))
      (node (ref "X3") (pin "3") (pinfunction "D+_3") (pintype "bidirectional"))
    )
    (net (code "64") (name "USB1_VBUS") (class "Default")
      (node (ref "C45") (pin "1") (pinfunction "1_1") (pintype "passive"))
      (node (ref "C46") (pin "1") (pinfunction "1_1") (pintype "passive"))
      (node (ref "C61") (pin "2") (pinfunction "2_2") (pintype "passive"))
      (node (ref "L5") (pin "1") (pinfunction "1_1") (pintype "passive"))
      (node (ref "R1100") (pin "2") (pinfunction "2_2") (pintype "passive"))
      (node (ref "R119") (pin "1") (pinfunction "1_1") (pintype "passive"))
      (node (ref "R121") (pin "1") (pinfunction "1_1") (pintype "passive"))
      (node (ref "U8") (pin "4") (pinfunction "OUT_4") (pintype "output"))
    )
    (net (code "65") (name "USB_DC") (class "Default")
      (node (ref "R112") (pin "1") (pinfunction "1_1") (pintype "passive"))
      (node (ref "U2") (pin "Y8") (pinfunction "VIN_USB_0_Y8") (pintype "power_in"))
      (node (ref "U2") (pin "Y9") (pinfunction "VIN_USB_1_Y9") (pintype "power_in"))
    )
    (net (code "66") (name "VDD_1V8") (class "Default")
      (node (ref "U2") (pin "D10") (pinfunction "VDD_1V84_D10") (pintype "bidirectional"))
      (node (ref "U2") (pin "E9") (pinfunction "VDD_1V83_E9") (pintype "bidirectional"))
      (node (ref "U2") (pin "N16") (pinfunction "VOUT_LDO3_1P8V_0_N16") (pintype "power_in"))
      (node (ref "U2") (pin "R16") (pinfunction "VOUT_LDO3_1P8V_1_R16") (pintype "power_in"))
    )
    (net (code "67") (name "VDD_3V3AUX") (class "Default")
      (node (ref "PWR") (pin "A") (pinfunction "A_A") (pintype "passive"))
      (node (ref "U2") (pin "Y11") (pinfunction "VOUT_LDO2_3P3V_Y11") (pintype "power_in"))
    )
    (net (code "68") (name "VDD_RTC") (class "Default")
      (node (ref "U2") (pin "E14") (pinfunction "VDD_RTC3_E14") (pintype "bidirectional"))
      (node (ref "U3") (pin "5") (pinfunction "VCC_5") (pintype "power_in"))
    )
    (net (code "69") (name "VIN_BAT_0") (class "Default")
      (node (ref "U2") (pin "Y2") (pinfunction "VIN_BAT_0_Y2") (pintype "power_in"))
    )
    (net (code "70") (name "VIN_BAT_1") (class "Default")
      (node (ref "U2") (pin "Y3") (pinfunction "VIN_BAT_1_Y3") (pintype "power_in"))
    )
    (net (code "71") (name "unconnected-(U2-PadH16)") (class "Default")
      (node (ref "U2") (pin "H16") (pinfunction "H16_H16") (pintype "bidirectional"))
    )
    (net (code "72") (name "unconnected-(U2-PadH17)") (class "Default")
      (node (ref "U2") (pin "H17") (pinfunction "H17_H17") (pintype "bidirectional"))
    )
    (net (code "73") (name "unconnected-(U2-PadH18)") (class "Default")
      (node (ref "U2") (pin "H18") (pinfunction "H18_H18") (pintype "bidirectional"))
    )
    (net (code "74") (name "unconnected-(U2-PadJ15)") (class "Default")
      (node (ref "U2") (pin "J15") (pinfunction "J15_J15") (pintype "bidirectional"))
    )
    (net (code "75") (name "unconnected-(U2-PadJ16)") (class "Default")
      (node (ref "U2") (pin "J16") (pinfunction "J16_J16") (pintype "bidirectional"))
    )
    (net (code "76") (name "unconnected-(U2-PadJ17)") (class "Default")
      (node (ref "U2") (pin "J17") (pinfunction "J17_J17") (pintype "bidirectional"))
    )
    (net (code "77") (name "unconnected-(U2-PadJ18)") (class "Default")
      (node (ref "U2") (pin "J18") (pinfunction "J18_J18") (pintype "bidirectional"))
    )
    (net (code "78") (name "unconnected-(U2-PadK15)") (class "Default")
      (node (ref "U2") (pin "K15") (pinfunction "K15_K15") (pintype "bidirectional"))
    )
    (net (code "79") (name "unconnected-(U2-PadK16)") (class "Default")
      (node (ref "U2") (pin "K16") (pinfunction "K16_K16") (pintype "bidirectional"))
    )
    (net (code "80") (name "unconnected-(U2-PadK17)") (class "Default")
      (node (ref "U2") (pin "K17") (pinfunction "K17_K17") (pintype "bidirectional"))
    )
    (net (code "81") (name "unconnected-(U2-PadK18)") (class "Default")
      (node (ref "U2") (pin "K18") (pinfunction "K18_K18") (pintype "bidirectional"))
    )
    (net (code "82") (name "unconnected-(U2-PadL15)") (class "Default")
      (node (ref "U2") (pin "L15") (pinfunction "L15_L15") (pintype "bidirectional"))
    )
    (net (code "83") (name "unconnected-(U2-PadL16)") (class "Default")
      (node (ref "U2") (pin "L16") (pinfunction "L16_L16") (pintype "bidirectional"))
    )
    (net (code "84") (name "unconnected-(U2-PadL17)") (class "Default")
      (node (ref "U2") (pin "L17") (pinfunction "L17_L17") (pintype "bidirectional"))
    )
    (net (code "85") (name "unconnected-(U2-PadL18)") (class "Default")
      (node (ref "U2") (pin "L18") (pinfunction "L18_L18") (pintype "bidirectional"))
    )
    (net (code "86") (name "unconnected-(U2-PadM16)") (class "Default")
      (node (ref "U2") (pin "M16") (pinfunction "M16_M16") (pintype "bidirectional"))
    )
    (net (code "87") (name "unconnected-(U2-PadM17)") (class "Default")
      (node (ref "U2") (pin "M17") (pinfunction "M17_M17") (pintype "bidirectional"))
    )
    (net (code "88") (name "unconnected-(U2-PadM18)") (class "Default")
      (node (ref "U2") (pin "M18") (pinfunction "M18_M18") (pintype "bidirectional"))
    )
    (net (code "89") (name "unconnected-(U2A-BAT_TEMP-PadW1)") (class "Default")
      (node (ref "U2") (pin "W1") (pinfunction "BAT_TEMP_W1") (pintype "bidirectional"))
    )
    (net (code "90") (name "unconnected-(U2A-BAT_VOLT-PadY1)") (class "Default")
      (node (ref "U2") (pin "Y1") (pinfunction "BAT_VOLT_Y1") (pintype "bidirectional"))
    )
    (net (code "91") (name "unconnected-(U2A-L1_IN-PadY14)") (class "Default")
      (node (ref "U2") (pin "Y14") (pinfunction "L1_IN_Y14") (pintype "bidirectional"))
    )
    (net (code "92") (name "unconnected-(U2A-L1_OUT-PadY13)") (class "Default")
      (node (ref "U2") (pin "Y13") (pinfunction "L1_OUT_Y13") (pintype "bidirectional"))
    )
    (net (code "93") (name "unconnected-(U2A-L2_IN-PadY17)") (class "Default")
      (node (ref "U2") (pin "Y17") (pinfunction "L2_IN_Y17") (pintype "bidirectional"))
    )
    (net (code "94") (name "unconnected-(U2A-L2_OUT-PadY16)") (class "Default")
      (node (ref "U2") (pin "Y16") (pinfunction "L2_OUT_Y16") (pintype "bidirectional"))
    )
    (net (code "95") (name "unconnected-(U2A-L3_IN-PadY20)") (class "Default")
      (node (ref "U2") (pin "Y20") (pinfunction "L3_IN_Y20") (pintype "bidirectional"))
    )
    (net (code "96") (name "unconnected-(U2A-L3_OUT-PadY19)") (class "Default")
      (node (ref "U2") (pin "Y19") (pinfunction "L3_OUT_Y19") (pintype "bidirectional"))
    )
    (net (code "97") (name "unconnected-(U2B-EHRPWM1A_U14-PadU14)") (class "Default")
      (node (ref "U2") (pin "U14") (pinfunction "EHRPWM1A_U14_U14") (pintype "bidirectional"))
    )
    (net (code "98") (name "unconnected-(U2B-EHRPWM1B_T14-PadT14)") (class "Default")
      (node (ref "U2") (pin "T14") (pinfunction "EHRPWM1B_T14_T14") (pintype "bidirectional"))
    )
    (net (code "99") (name "unconnected-(U2B-EHRPWM2A_U10-PadU10)") (class "Default")
      (node (ref "U2") (pin "U10") (pinfunction "EHRPWM2A_U10_U10") (pintype "bidirectional"))
    )
    (net (code "100") (name "unconnected-(U2B-EHRPWM2B_T10-PadT10)") (class "Default")
      (node (ref "U2") (pin "T10") (pinfunction "EHRPWM2B_T10_T10") (pintype "bidirectional"))
    )
    (net (code "101") (name "unconnected-(U2B-EMMCRST_GPIO1_20_R14-PadR14)") (class "Default")
      (node (ref "U2") (pin "R14") (pinfunction "EMMCRST_GPIO1_20_R14_R14") (pintype "bidirectional"))
    )
    (net (code "102") (name "unconnected-(U2B-GPIO0_7_C18-PadC18)") (class "Default")
      (node (ref "U2") (pin "C18") (pinfunction "GPIO0_7_C18_C18") (pintype "bidirectional"))
    )
    (net (code "103") (name "unconnected-(U2B-GPIO0_19_A15-PadA15)") (class "Default")
      (node (ref "U2") (pin "A15") (pinfunction "GPIO0_19_A15_A15") (pintype "bidirectional"))
    )
    (net (code "104") (name "unconnected-(U2B-GPIO0_20_D14-PadD14)") (class "Default")
      (node (ref "U2") (pin "D14") (pinfunction "GPIO0_20_D14_D14") (pintype "bidirectional"))
    )
    (net (code "105") (name "unconnected-(U2B-GPIO0_26_T11-PadT11)") (class "Default")
      (node (ref "U2") (pin "T11") (pinfunction "GPIO0_26_T11_T11") (pintype "bidirectional"))
    )
    (net (code "106") (name "unconnected-(U2B-GPIO0_27_U12-PadU12)") (class "Default")
      (node (ref "U2") (pin "U12") (pinfunction "GPIO0_27_U12_U12") (pintype "bidirectional"))
    )
    (net (code "107") (name "unconnected-(U2B-GPIO1_12_T12-PadT12)") (class "Default")
      (node (ref "U2") (pin "T12") (pinfunction "GPIO1_12_T12_T12") (pintype "bidirectional"))
    )
    (net (code "108") (name "unconnected-(U2B-GPIO1_13_R12-PadR12)") (class "Default")
      (node (ref "U2") (pin "R12") (pinfunction "GPIO1_13_R12_R12") (pintype "bidirectional"))
    )
    (net (code "109") (name "unconnected-(U2B-GPIO1_14_V13-PadV13)") (class "Default")
      (node (ref "U2") (pin "V13") (pinfunction "GPIO1_14_V13_V13") (pintype "bidirectional"))
    )
    (net (code "110") (name "unconnected-(U2B-GPIO1_15_U13-PadU13)") (class "Default")
      (node (ref "U2") (pin "U13") (pinfunction "GPIO1_15_U13_U13") (pintype "bidirectional"))
    )
    (net (code "111") (name "unconnected-(U2B-GPIO1_16_R13-PadR13)") (class "Default")
      (node (ref "U2") (pin "R13") (pinfunction "GPIO1_16_R13_R13") (pintype "bidirectional"))
    )
    (net (code "112") (name "unconnected-(U2B-GPIO1_17_V14-PadV14)") (class "Default")
      (node (ref "U2") (pin "V14") (pinfunction "GPIO1_17_V14_V14") (pintype "bidirectional"))
    )
    (net (code "113") (name "unconnected-(U2B-GPIO1_28_U18-PadU18)") (class "Default")
      (node (ref "U2") (pin "U18") (pinfunction "GPIO1_28_U18_U18") (pintype "bidirectional"))
    )
    (net (code "114") (name "unconnected-(U2B-GPIO1_29_V6-PadV6)") (class "Default")
      (node (ref "U2") (pin "V6") (pinfunction "GPIO1_29_V6_V6") (pintype "bidirectional"))
    )
    (net (code "115") (name "unconnected-(U2B-GPIO2_0_T13-PadT13)") (class "Default")
      (node (ref "U2") (pin "T13") (pinfunction "GPIO2_0_T13_T13") (pintype "bidirectional"))
    )
    (net (code "116") (name "unconnected-(U2B-GPIO2_1_V12-PadV12)") (class "Default")
      (node (ref "U2") (pin "V12") (pinfunction "GPIO2_1_V12_V12") (pintype "bidirectional"))
    )
    (net (code "117") (name "unconnected-(U2B-GPIO3_18_B12-PadB12)") (class "Default")
      (node (ref "U2") (pin "B12") (pinfunction "GPIO3_18_B12_B12") (pintype "bidirectional"))
    )
    (net (code "118") (name "unconnected-(U2B-GPIO3_19_C13-PadC13)") (class "Default")
      (node (ref "U2") (pin "C13") (pinfunction "GPIO3_19_C13_C13") (pintype "bidirectional"))
    )
    (net (code "119") (name "unconnected-(U2B-GPIO3_20_D13-PadD13)") (class "Default")
      (node (ref "U2") (pin "D13") (pinfunction "GPIO3_20_D13_D13") (pintype "bidirectional"))
    )
    (net (code "120") (name "unconnected-(U2B-GPIO3_21_A14-PadA14)") (class "Default")
      (node (ref "U2") (pin "A14") (pinfunction "GPIO3_21_A14_A14") (pintype "bidirectional"))
    )
    (net (code "121") (name "unconnected-(U2B-I2C1_SCL_A16-PadA16)") (class "Default")
      (node (ref "U2") (pin "A16") (pinfunction "I2C1_SCL_A16_A16") (pintype "bidirectional"))
    )
    (net (code "122") (name "unconnected-(U2B-I2C1_SDA_B16-PadB16)") (class "Default")
      (node (ref "U2") (pin "B16") (pinfunction "I2C1_SDA_B16_B16") (pintype "bidirectional"))
    )
    (net (code "123") (name "unconnected-(U2B-I2C2_SCL_D17-PadD17)") (class "Default")
      (node (ref "U2") (pin "D17") (pinfunction "I2C2_SCL_D17_D17") (pintype "bidirectional"))
    )
    (net (code "124") (name "unconnected-(U2B-I2C2_SDA_D18-PadD18)") (class "Default")
      (node (ref "U2") (pin "D18") (pinfunction "I2C2_SDA_D18_D18") (pintype "bidirectional"))
    )
    (net (code "125") (name "unconnected-(U2B-JTAG_EMU0-PadC14)") (class "Default")
      (node (ref "U2") (pin "C14") (pinfunction "JTAG_EMU0_C14") (pintype "bidirectional"))
    )
    (net (code "126") (name "unconnected-(U2B-JTAG_EMU1-PadB14)") (class "Default")
      (node (ref "U2") (pin "B14") (pinfunction "JTAG_EMU1_B14") (pintype "bidirectional"))
    )
    (net (code "127") (name "unconnected-(U2B-JTAG_TCK-PadA12)") (class "Default")
      (node (ref "U2") (pin "A12") (pinfunction "JTAG_TCK_A12") (pintype "bidirectional"))
    )
    (net (code "128") (name "unconnected-(U2B-JTAG_TDI-PadB11)") (class "Default")
      (node (ref "U2") (pin "B11") (pinfunction "JTAG_TDI_B11") (pintype "bidirectional"))
    )
    (net (code "129") (name "unconnected-(U2B-JTAG_TDO-PadA11)") (class "Default")
      (node (ref "U2") (pin "A11") (pinfunction "JTAG_TDO_A11") (pintype "bidirectional"))
    )
    (net (code "130") (name "unconnected-(U2B-JTAG_TMS-PadC11)") (class "Default")
      (node (ref "U2") (pin "C11") (pinfunction "JTAG_TMS_C11") (pintype "bidirectional"))
    )
    (net (code "131") (name "unconnected-(U2B-MMC1_CLK_U9-PadU9)") (class "Default")
      (node (ref "U2") (pin "U9") (pinfunction "MMC1_CLK_U9_U9") (pintype "bidirectional"))
    )
    (net (code "132") (name "unconnected-(U2B-MMC1_CMD_V9-PadV9)") (class "Default")
      (node (ref "U2") (pin "V9") (pinfunction "MMC1_CMD_V9_V9") (pintype "bidirectional"))
    )
    (net (code "133") (name "unconnected-(U2B-MMC1_DAT0_U7-PadU7)") (class "Default")
      (node (ref "U2") (pin "U7") (pinfunction "MMC1_DAT0_U7_U7") (pintype "bidirectional"))
    )
    (net (code "134") (name "unconnected-(U2B-MMC1_DAT1_V7-PadV7)") (class "Default")
      (node (ref "U2") (pin "V7") (pinfunction "MMC1_DAT1_V7_V7") (pintype "bidirectional"))
    )
    (net (code "135") (name "unconnected-(U2B-MMC1_DAT2_R8-PadR8)") (class "Default")
      (node (ref "U2") (pin "R8") (pinfunction "MMC1_DAT2_R8_R8") (pintype "bidirectional"))
    )
    (net (code "136") (name "unconnected-(U2B-MMC1_DAT3_T8-PadT8)") (class "Default")
      (node (ref "U2") (pin "T8") (pinfunction "MMC1_DAT3_T8_T8") (pintype "bidirectional"))
    )
    (net (code "137") (name "unconnected-(U2B-MMC1_DAT4_U8-PadU8)") (class "Default")
      (node (ref "U2") (pin "U8") (pinfunction "MMC1_DAT4_U8_U8") (pintype "bidirectional"))
    )
    (net (code "138") (name "unconnected-(U2B-MMC1_DAT5_V8-PadV8)") (class "Default")
      (node (ref "U2") (pin "V8") (pinfunction "MMC1_DAT5_V8_V8") (pintype "bidirectional"))
    )
    (net (code "139") (name "unconnected-(U2B-MMC1_DAT6_R9-PadR9)") (class "Default")
      (node (ref "U2") (pin "R9") (pinfunction "MMC1_DAT6_R9_R9") (pintype "bidirectional"))
    )
    (net (code "140") (name "unconnected-(U2B-MMC1_DAT7_T9-PadT9)") (class "Default")
      (node (ref "U2") (pin "T9") (pinfunction "MMC1_DAT7_T9_T9") (pintype "bidirectional"))
    )
    (net (code "141") (name "unconnected-(U2B-OSC1_GND-PadG20)") (class "Default")
      (node (ref "U2") (pin "G20") (pinfunction "OSC1_GND_G20") (pintype "bidirectional"))
    )
    (net (code "142") (name "unconnected-(U2B-OSC1_IN-PadH20)") (class "Default")
      (node (ref "U2") (pin "H20") (pinfunction "OSC1_IN_H20") (pintype "bidirectional"))
    )
    (net (code "143") (name "unconnected-(U2B-OSC1_OUT-PadF20)") (class "Default")
      (node (ref "U2") (pin "F20") (pinfunction "OSC1_OUT_F20") (pintype "bidirectional"))
    )
    (net (code "144") (name "unconnected-(U2B-SPI1_CLK_A13-PadA13)") (class "Default")
      (node (ref "U2") (pin "A13") (pinfunction "SPI1_CLK_A13_A13") (pintype "bidirectional"))
    )
    (net (code "145") (name "unconnected-(U2B-SPI1_CS0_C12-PadC12)") (class "Default")
      (node (ref "U2") (pin "C12") (pinfunction "SPI1_CS0_C12_C12") (pintype "bidirectional"))
    )
    (net (code "146") (name "unconnected-(U2B-SPI1_D0_B13-PadB13)") (class "Default")
      (node (ref "U2") (pin "B13") (pinfunction "SPI1_D0_B13_B13") (pintype "bidirectional"))
    )
    (net (code "147") (name "unconnected-(U2B-SPI1_D1_D12-PadD12)") (class "Default")
      (node (ref "U2") (pin "D12") (pinfunction "SPI1_D1_D12_D12") (pintype "bidirectional"))
    )
    (net (code "148") (name "unconnected-(U2B-TIMER4_R7-PadR7)") (class "Default")
      (node (ref "U2") (pin "R7") (pinfunction "TIMER4_R7_R7") (pintype "bidirectional"))
    )
    (net (code "149") (name "unconnected-(U2B-TIMER5_T6-PadT6)") (class "Default")
      (node (ref "U2") (pin "T6") (pinfunction "TIMER5_T6_T6") (pintype "bidirectional"))
    )
    (net (code "150") (name "unconnected-(U2B-TIMER6_U6-PadU6)") (class "Default")
      (node (ref "U2") (pin "U6") (pinfunction "TIMER6_U6_U6") (pintype "bidirectional"))
    )
    (net (code "151") (name "unconnected-(U2B-TIMER7_T7-PadT7)") (class "Default")
      (node (ref "U2") (pin "T7") (pinfunction "TIMER7_T7_T7") (pintype "bidirectional"))
    )
    (net (code "152") (name "unconnected-(U2B-UART0_CTSN_E18-PadE18)") (class "Default")
      (node (ref "U2") (pin "E18") (pinfunction "UART0_CTSN_E18_E18") (pintype "bidirectional"))
    )
    (net (code "153") (name "unconnected-(U2B-UART0_RTSN_E17-PadE17)") (class "Default")
      (node (ref "U2") (pin "E17") (pinfunction "UART0_RTSN_E17_E17") (pintype "bidirectional"))
    )
    (net (code "154") (name "unconnected-(U2B-UART0_RXD_E15-PadE15)") (class "Default")
      (node (ref "U2") (pin "E15") (pinfunction "UART0_RXD_E15_E15") (pintype "bidirectional"))
    )
    (net (code "155") (name "unconnected-(U2B-UART0_TXD_E16-PadE16)") (class "Default")
      (node (ref "U2") (pin "E16") (pinfunction "UART0_TXD_E16_E16") (pintype "bidirectional"))
    )
    (net (code "156") (name "unconnected-(U2B-UART1_RXD_D16-PadD16)") (class "Default")
      (node (ref "U2") (pin "D16") (pinfunction "UART1_RXD_D16_D16") (pintype "bidirectional"))
    )
    (net (code "157") (name "unconnected-(U2B-UART1_TXD_D15-PadD15)") (class "Default")
      (node (ref "U2") (pin "D15") (pinfunction "UART1_TXD_D15_D15") (pintype "bidirectional"))
    )
    (net (code "158") (name "unconnected-(U2B-UART2_RXD_A17-PadA17)") (class "Default")
      (node (ref "U2") (pin "A17") (pinfunction "UART2_RXD_A17_A17") (pintype "bidirectional"))
    )
    (net (code "159") (name "unconnected-(U2B-UART2_TXD_B17-PadB17)") (class "Default")
      (node (ref "U2") (pin "B17") (pinfunction "UART2_TXD_B17_B17") (pintype "bidirectional"))
    )
    (net (code "160") (name "unconnected-(U2B-UART4_RXD_T17-PadT17)") (class "Default")
      (node (ref "U2") (pin "T17") (pinfunction "UART4_RXD_T17_T17") (pintype "bidirectional"))
    )
    (net (code "161") (name "unconnected-(U2B-UART4_TXD_U17-PadU17)") (class "Default")
      (node (ref "U2") (pin "U17") (pinfunction "UART4_TXD_U17_U17") (pintype "bidirectional"))
    )
    (net (code "162") (name "unconnected-(U2C-ADC_VREFP-PadB9)") (class "Default")
      (node (ref "U2") (pin "B9") (pinfunction "ADC_VREFP_B9") (pintype "bidirectional"))
    )
    (net (code "163") (name "unconnected-(U2C-AIN0-PadB6)") (class "Default")
      (node (ref "U2") (pin "B6") (pinfunction "AIN0_B6") (pintype "bidirectional"))
    )
    (net (code "164") (name "unconnected-(U2C-AIN1-PadC7)") (class "Default")
      (node (ref "U2") (pin "C7") (pinfunction "AIN1_C7") (pintype "bidirectional"))
    )
    (net (code "165") (name "unconnected-(U2C-AIN2-PadB7)") (class "Default")
      (node (ref "U2") (pin "B7") (pinfunction "AIN2_B7") (pintype "bidirectional"))
    )
    (net (code "166") (name "unconnected-(U2C-AIN3-PadA7)") (class "Default")
      (node (ref "U2") (pin "A7") (pinfunction "AIN3_A7") (pintype "bidirectional"))
    )
    (net (code "167") (name "unconnected-(U2C-AIN4-PadC8)") (class "Default")
      (node (ref "U2") (pin "C8") (pinfunction "AIN4_C8") (pintype "bidirectional"))
    )
    (net (code "168") (name "unconnected-(U2C-AIN5-PadB8)") (class "Default")
      (node (ref "U2") (pin "B8") (pinfunction "AIN5_B8") (pintype "bidirectional"))
    )
    (net (code "169") (name "unconnected-(U2C-AIN6-PadA8)") (class "Default")
      (node (ref "U2") (pin "A8") (pinfunction "AIN6_A8") (pintype "bidirectional"))
    )
    (net (code "170") (name "unconnected-(U2C-AIN7-PadC9)") (class "Default")
      (node (ref "U2") (pin "C9") (pinfunction "AIN7_C9") (pintype "bidirectional"))
    )
    (net (code "171") (name "unconnected-(U2C-HDMIDIS_GPIO1_27_V17-PadV17)") (class "Default")
      (node (ref "U2") (pin "V17") (pinfunction "HDMIDIS_GPIO1_27_V17_V17") (pintype "bidirectional"))
    )
    (net (code "172") (name "unconnected-(U2C-HDMIINT_GPIO1_25_U16-PadU16)") (class "Default")
      (node (ref "U2") (pin "U16") (pinfunction "HDMIINT_GPIO1_25_U16_U16") (pintype "bidirectional"))
    )
    (net (code "173") (name "unconnected-(U2C-LCD_DE_R6-PadR6)") (class "Default")
      (node (ref "U2") (pin "R6") (pinfunction "LCD_DE_R6_R6") (pintype "bidirectional"))
    )
    (net (code "174") (name "unconnected-(U2C-LCD_HSYNC_R5-PadR5)") (class "Default")
      (node (ref "U2") (pin "R5") (pinfunction "LCD_HSYNC_R5_R5") (pintype "bidirectional"))
    )
    (net (code "175") (name "unconnected-(U2C-LCD_PCLK_V5-PadV5)") (class "Default")
      (node (ref "U2") (pin "V5") (pinfunction "LCD_PCLK_V5_V5") (pintype "bidirectional"))
    )
    (net (code "176") (name "unconnected-(U2C-LCD_VSYNC_U5-PadU5)") (class "Default")
      (node (ref "U2") (pin "U5") (pinfunction "LCD_VSYNC_U5_U5") (pintype "bidirectional"))
    )
    (net (code "177") (name "unconnected-(U2C-USB0_CE-PadM15)") (class "Default")
      (node (ref "U2") (pin "M15") (pinfunction "USB0_CE_M15") (pintype "bidirectional"))
    )
    (net (code "178") (name "unconnected-(U2C-USB0_DRVVBUS-PadF16)") (class "Default")
      (node (ref "U2") (pin "F16") (pinfunction "USB0_DRVVBUS_F16") (pintype "bidirectional"))
    )
    (net (code "179") (name "unconnected-(U2C-USB1OC_GPIO1_26_T16-PadT16)") (class "Default")
      (node (ref "U2") (pin "T16") (pinfunction "USB1OC_GPIO1_26_T16_T16") (pintype "bidirectional"))
    )
    (net (code "180") (name "unconnected-(U2C-USB1_CE-PadP18)") (class "Default")
      (node (ref "U2") (pin "P18") (pinfunction "USB1_CE_P18") (pintype "bidirectional"))
    )
    (net (code "181") (name "unconnected-(U2C-USB1_DRVVBUS-PadF15)") (class "Default")
      (node (ref "U2") (pin "F15") (pinfunction "USB1_DRVVBUS_F15") (pintype "bidirectional"))
    )
    (net (code "182") (name "unconnected-(U2C-VOUT_ADC_1P8V_0-PadA4)") (class "Default")
      (node (ref "U2") (pin "A4") (pinfunction "VOUT_ADC_1P8V_0_A4") (pintype "bidirectional"))
    )
    (net (code "183") (name "unconnected-(U2C-VOUT_ADC_1P8V_1-PadA5)") (class "Default")
      (node (ref "U2") (pin "A5") (pinfunction "VOUT_ADC_1P8V_1_A5") (pintype "bidirectional"))
    )
    (net (code "184") (name "unconnected-(U2C-VSSA_ADC_0-PadA6)") (class "Default")
      (node (ref "U2") (pin "A6") (pinfunction "VSSA_ADC_0_A6") (pintype "bidirectional"))
    )
    (net (code "185") (name "unconnected-(U2C-VSSA_ADC_1-PadA9)") (class "Default")
      (node (ref "U2") (pin "A9") (pinfunction "VSSA_ADC_1_A9") (pintype "bidirectional"))
    )
    (net (code "186") (name "unconnected-(U2C-VSSA_ADC_2-PadE8)") (class "Default")
      (node (ref "U2") (pin "E8") (pinfunction "VSSA_ADC_2_E8") (pintype "bidirectional"))
    )
    (net (code "187") (name "unconnected-(U2E-CAP_VBB_MPU-PadC10)") (class "Default")
      (node (ref "U2") (pin "C10") (pinfunction "CAP_VBB_MPU_C10") (pintype "bidirectional"))
    )
    (net (code "188") (name "unconnected-(U2E-CAP_VDD_RTC-PadD6)") (class "Default")
      (node (ref "U2") (pin "D6") (pinfunction "CAP_VDD_RTC_D6") (pintype "bidirectional"))
    )
    (net (code "189") (name "unconnected-(U2E-CAP_VDD_SRAM_COR-PadD9)") (class "Default")
      (node (ref "U2") (pin "D9") (pinfunction "CAP_VDD_SRAM_COR_D9") (pintype "bidirectional"))
    )
    (net (code "190") (name "unconnected-(U2E-CAP_VDD_SRAM_MPU-PadD11)") (class "Default")
      (node (ref "U2") (pin "D11") (pinfunction "CAP_VDD_SRAM_MPU_D11") (pintype "bidirectional"))
    )
    (net (code "191") (name "unconnected-(U2E-TESTOUT-PadA3)") (class "Default")
      (node (ref "U2") (pin "A3") (pinfunction "TESTOUT_A3") (pintype "bidirectional"))
    )
    (net (code "192") (name "unconnected-(U2E-VDDA_ADC-PadD8)") (class "Default")
      (node (ref "U2") (pin "D8") (pinfunction "VDDA_ADC_D8") (pintype "bidirectional"))
    )
    (net (code "193") (name "unconnected-(U2E-VDDS_DDR1-PadE5)") (class "Default")
      (node (ref "U2") (pin "E5") (pinfunction "VDDS_DDR1_E5") (pintype "bidirectional"))
    )
    (net (code "194") (name "unconnected-(U2E-VDDS_DDR2-PadF5)") (class "Default")
      (node (ref "U2") (pin "F5") (pinfunction "VDDS_DDR2_F5") (pintype "bidirectional"))
    )
    (net (code "195") (name "unconnected-(U2E-VDDS_DDR3-PadG5)") (class "Default")
      (node (ref "U2") (pin "G5") (pinfunction "VDDS_DDR3_G5") (pintype "bidirectional"))
    )
    (net (code "196") (name "unconnected-(U2E-VDDS_DDR4-PadH5)") (class "Default")
      (node (ref "U2") (pin "H5") (pinfunction "VDDS_DDR4_H5") (pintype "bidirectional"))
    )
    (net (code "197") (name "unconnected-(U2E-VDDS_DDR5-PadJ5)") (class "Default")
      (node (ref "U2") (pin "J5") (pinfunction "VDDS_DDR5_J5") (pintype "bidirectional"))
    )
    (net (code "198") (name "unconnected-(U2E-VDDS_DDR6-PadK5)") (class "Default")
      (node (ref "U2") (pin "K5") (pinfunction "VDDS_DDR6_K5") (pintype "bidirectional"))
    )
    (net (code "199") (name "unconnected-(U2E-VDDS_DDR7-PadL5)") (class "Default")
      (node (ref "U2") (pin "L5") (pinfunction "VDDS_DDR7_L5") (pintype "bidirectional"))
    )
    (net (code "200") (name "unconnected-(U2E-VDD_3V3A1-PadE10)") (class "Default")
      (node (ref "U2") (pin "E10") (pinfunction "VDD_3V3A1_E10") (pintype "bidirectional"))
    )
    (net (code "201") (name "unconnected-(U2E-VDD_3V3A2-PadE11)") (class "Default")
      (node (ref "U2") (pin "E11") (pinfunction "VDD_3V3A2_E11") (pintype "bidirectional"))
    )
    (net (code "202") (name "unconnected-(U2E-VDD_3V3A3-PadE12)") (class "Default")
      (node (ref "U2") (pin "E12") (pinfunction "VDD_3V3A3_E12") (pintype "bidirectional"))
    )
    (net (code "203") (name "unconnected-(U2E-VDD_3V3A4-PadE13)") (class "Default")
      (node (ref "U2") (pin "E13") (pinfunction "VDD_3V3A4_E13") (pintype "bidirectional"))
    )
    (net (code "204") (name "unconnected-(U2E-VDD_3V3A5-PadF14)") (class "Default")
      (node (ref "U2") (pin "F14") (pinfunction "VDD_3V3A5_F14") (pintype "bidirectional"))
    )
    (net (code "205") (name "unconnected-(U2E-VDD_3V3A6-PadG14)") (class "Default")
      (node (ref "U2") (pin "G14") (pinfunction "VDD_3V3A6_G14") (pintype "bidirectional"))
    )
    (net (code "206") (name "unconnected-(U2E-VDD_3V3A7-PadH14)") (class "Default")
      (node (ref "U2") (pin "H14") (pinfunction "VDD_3V3A7_H14") (pintype "bidirectional"))
    )
    (net (code "207") (name "unconnected-(U2E-VDD_3V3A8-PadJ14)") (class "Default")
      (node (ref "U2") (pin "J14") (pinfunction "VDD_3V3A8_J14") (pintype "bidirectional"))
    )
    (net (code "208") (name "unconnected-(U2E-VDD_3V3A9-PadK14)") (class "Default")
      (node (ref "U2") (pin "K14") (pinfunction "VDD_3V3A9_K14") (pintype "bidirectional"))
    )
    (net (code "209") (name "unconnected-(U2E-VDD_3V3A10-PadL14)") (class "Default")
      (node (ref "U2") (pin "L14") (pinfunction "VDD_3V3A10_L14") (pintype "bidirectional"))
    )
    (net (code "210") (name "unconnected-(U2E-VDD_3V3A11-PadN5)") (class "Default")
      (node (ref "U2") (pin "N5") (pinfunction "VDD_3V3A11_N5") (pintype "bidirectional"))
    )
    (net (code "211") (name "unconnected-(U2E-VDD_3V3A12-PadN15)") (class "Default")
      (node (ref "U2") (pin "N15") (pinfunction "VDD_3V3A12_N15") (pintype "bidirectional"))
    )
    (net (code "212") (name "unconnected-(U2E-VDD_3V3A13-PadP5)") (class "Default")
      (node (ref "U2") (pin "P5") (pinfunction "VDD_3V3A13_P5") (pintype "bidirectional"))
    )
    (net (code "213") (name "unconnected-(U2E-VDD_3V3A14-PadP6)") (class "Default")
      (node (ref "U2") (pin "P6") (pinfunction "VDD_3V3A14_P6") (pintype "bidirectional"))
    )
    (net (code "214") (name "unconnected-(U2E-VDD_3V3A15-PadP7)") (class "Default")
      (node (ref "U2") (pin "P7") (pinfunction "VDD_3V3A15_P7") (pintype "bidirectional"))
    )
    (net (code "215") (name "unconnected-(U2E-VDD_3V3A16-PadP8)") (class "Default")
      (node (ref "U2") (pin "P8") (pinfunction "VDD_3V3A16_P8") (pintype "bidirectional"))
    )
    (net (code "216") (name "unconnected-(U2E-VDD_3V3A17-PadP10)") (class "Default")
      (node (ref "U2") (pin "P10") (pinfunction "VDD_3V3A17_P10") (pintype "bidirectional"))
    )
    (net (code "217") (name "unconnected-(U2E-VDD_3V3A18-PadP11)") (class "Default")
      (node (ref "U2") (pin "P11") (pinfunction "VDD_3V3A18_P11") (pintype "bidirectional"))
    )
    (net (code "218") (name "unconnected-(U2E-VDD_3V3A19-PadP12)") (class "Default")
      (node (ref "U2") (pin "P12") (pinfunction "VDD_3V3A19_P12") (pintype "bidirectional"))
    )
    (net (code "219") (name "unconnected-(U2E-VDD_3V3A20-PadP13)") (class "Default")
      (node (ref "U2") (pin "P13") (pinfunction "VDD_3V3A20_P13") (pintype "bidirectional"))
    )
    (net (code "220") (name "unconnected-(U2E-VDD_3V3A21-PadR15)") (class "Default")
      (node (ref "U2") (pin "R15") (pinfunction "VDD_3V3A21_R15") (pintype "bidirectional"))
    )
    (net (code "221") (name "unconnected-(U2E-VDD_CORE1-PadF6)") (class "Default")
      (node (ref "U2") (pin "F6") (pinfunction "VDD_CORE1_F6") (pintype "bidirectional"))
    )
    (net (code "222") (name "unconnected-(U2E-VDD_CORE2-PadF7)") (class "Default")
      (node (ref "U2") (pin "F7") (pinfunction "VDD_CORE2_F7") (pintype "bidirectional"))
    )
    (net (code "223") (name "unconnected-(U2E-VDD_CORE3-PadG6)") (class "Default")
      (node (ref "U2") (pin "G6") (pinfunction "VDD_CORE3_G6") (pintype "bidirectional"))
    )
    (net (code "224") (name "unconnected-(U2E-VDD_CORE4-PadG7)") (class "Default")
      (node (ref "U2") (pin "G7") (pinfunction "VDD_CORE4_G7") (pintype "bidirectional"))
    )
    (net (code "225") (name "unconnected-(U2E-VDD_CORE5-PadG10)") (class "Default")
      (node (ref "U2") (pin "G10") (pinfunction "VDD_CORE5_G10") (pintype "bidirectional"))
    )
    (net (code "226") (name "unconnected-(U2E-VDD_CORE6-PadH11)") (class "Default")
      (node (ref "U2") (pin "H11") (pinfunction "VDD_CORE6_H11") (pintype "bidirectional"))
    )
    (net (code "227") (name "unconnected-(U2E-VDD_CORE7-PadJ12)") (class "Default")
      (node (ref "U2") (pin "J12") (pinfunction "VDD_CORE7_J12") (pintype "bidirectional"))
    )
    (net (code "228") (name "unconnected-(U2E-VDD_CORE8-PadK6)") (class "Default")
      (node (ref "U2") (pin "K6") (pinfunction "VDD_CORE8_K6") (pintype "bidirectional"))
    )
    (net (code "229") (name "unconnected-(U2E-VDD_CORE9-PadK8)") (class "Default")
      (node (ref "U2") (pin "K8") (pinfunction "VDD_CORE9_K8") (pintype "bidirectional"))
    )
    (net (code "230") (name "unconnected-(U2E-VDD_CORE10-PadK12)") (class "Default")
      (node (ref "U2") (pin "K12") (pinfunction "VDD_CORE10_K12") (pintype "bidirectional"))
    )
    (net (code "231") (name "unconnected-(U2E-VDD_CORE11-PadL6)") (class "Default")
      (node (ref "U2") (pin "L6") (pinfunction "VDD_CORE11_L6") (pintype "bidirectional"))
    )
    (net (code "232") (name "unconnected-(U2E-VDD_CORE12-PadL7)") (class "Default")
      (node (ref "U2") (pin "L7") (pinfunction "VDD_CORE12_L7") (pintype "bidirectional"))
    )
    (net (code "233") (name "unconnected-(U2E-VDD_CORE13-PadL8)") (class "Default")
      (node (ref "U2") (pin "L8") (pinfunction "VDD_CORE13_L8") (pintype "bidirectional"))
    )
    (net (code "234") (name "unconnected-(U2E-VDD_CORE14-PadL9)") (class "Default")
      (node (ref "U2") (pin "L9") (pinfunction "VDD_CORE14_L9") (pintype "bidirectional"))
    )
    (net (code "235") (name "unconnected-(U2E-VDD_CORE15-PadM11)") (class "Default")
      (node (ref "U2") (pin "M11") (pinfunction "VDD_CORE15_M11") (pintype "bidirectional"))
    )
    (net (code "236") (name "unconnected-(U2E-VDD_CORE16-PadM13)") (class "Default")
      (node (ref "U2") (pin "M13") (pinfunction "VDD_CORE16_M13") (pintype "bidirectional"))
    )
    (net (code "237") (name "unconnected-(U2E-VDD_CORE17-PadN8)") (class "Default")
      (node (ref "U2") (pin "N8") (pinfunction "VDD_CORE17_N8") (pintype "bidirectional"))
    )
    (net (code "238") (name "unconnected-(U2E-VDD_CORE18-PadN9)") (class "Default")
      (node (ref "U2") (pin "N9") (pinfunction "VDD_CORE18_N9") (pintype "bidirectional"))
    )
    (net (code "239") (name "unconnected-(U2E-VDD_CORE19-PadN12)") (class "Default")
      (node (ref "U2") (pin "N12") (pinfunction "VDD_CORE19_N12") (pintype "bidirectional"))
    )
    (net (code "240") (name "unconnected-(U2E-VDD_CORE20-PadN13)") (class "Default")
      (node (ref "U2") (pin "N13") (pinfunction "VDD_CORE20_N13") (pintype "bidirectional"))
    )
    (net (code "241") (name "unconnected-(U2E-VDD_MPU0-PadF10)") (class "Default")
      (node (ref "U2") (pin "F10") (pinfunction "VDD_MPU0_F10") (pintype "bidirectional"))
    )
    (net (code "242") (name "unconnected-(U2E-VDD_MPU1-PadF11)") (class "Default")
      (node (ref "U2") (pin "F11") (pinfunction "VDD_MPU1_F11") (pintype "bidirectional"))
    )
    (net (code "243") (name "unconnected-(U2E-VDD_MPU2-PadF12)") (class "Default")
      (node (ref "U2") (pin "F12") (pinfunction "VDD_MPU2_F12") (pintype "bidirectional"))
    )
    (net (code "244") (name "unconnected-(U2E-VDD_MPU3-PadF13)") (class "Default")
      (node (ref "U2") (pin "F13") (pinfunction "VDD_MPU3_F13") (pintype "bidirectional"))
    )
    (net (code "245") (name "unconnected-(U2E-VDD_MPU4-PadG13)") (class "Default")
      (node (ref "U2") (pin "G13") (pinfunction "VDD_MPU4_G13") (pintype "bidirectional"))
    )
    (net (code "246") (name "unconnected-(U2E-VDD_MPU5-PadH13)") (class "Default")
      (node (ref "U2") (pin "H13") (pinfunction "VDD_MPU5_H13") (pintype "bidirectional"))
    )
    (net (code "247") (name "unconnected-(U2E-VDD_MPU6-PadJ13)") (class "Default")
      (node (ref "U2") (pin "J13") (pinfunction "VDD_MPU6_J13") (pintype "bidirectional"))
    )
    (net (code "248") (name "unconnected-(U2E-VDD_MPU_MON-PadA2)") (class "Default")
      (node (ref "U2") (pin "A2") (pinfunction "VDD_MPU_MON_A2") (pintype "bidirectional"))
    )
    (net (code "249") (name "unconnected-(U2E-VDD_PLL1-PadE7)") (class "Default")
      (node (ref "U2") (pin "E7") (pinfunction "VDD_PLL1_E7") (pintype "bidirectional"))
    )
    (net (code "250") (name "unconnected-(U2E-VDD_PLL2-PadH15)") (class "Default")
      (node (ref "U2") (pin "H15") (pinfunction "VDD_PLL2_H15") (pintype "bidirectional"))
    )
    (net (code "251") (name "unconnected-(U2E-VDD_PLL3-PadR10)") (class "Default")
      (node (ref "U2") (pin "R10") (pinfunction "VDD_PLL3_R10") (pintype "bidirectional"))
    )
    (net (code "252") (name "unconnected-(U2E-VDD_PLL4-PadR11)") (class "Default")
      (node (ref "U2") (pin "R11") (pinfunction "VDD_PLL4_R11") (pintype "bidirectional"))
    )
    (net (code "253") (name "unconnected-(U2E-VDD_RTC1-PadD7)") (class "Default")
      (node (ref "U2") (pin "D7") (pinfunction "VDD_RTC1_D7") (pintype "bidirectional"))
    )
    (net (code "254") (name "unconnected-(U2E-VDD_RTC2-PadE6)") (class "Default")
      (node (ref "U2") (pin "E6") (pinfunction "VDD_RTC2_E6") (pintype "bidirectional"))
    )
    (net (code "255") (name "unconnected-(U2E-VDD_RTC4-PadF9)") (class "Default")
      (node (ref "U2") (pin "F9") (pinfunction "VDD_RTC4_F9") (pintype "bidirectional"))
    )
    (net (code "256") (name "unconnected-(U2E-VDD_RTC5-PadK13)") (class "Default")
      (node (ref "U2") (pin "K13") (pinfunction "VDD_RTC5_K13") (pintype "bidirectional"))
    )
    (net (code "257") (name "unconnected-(U2E-VDD_RTC6-PadN6)") (class "Default")
      (node (ref "U2") (pin "N6") (pinfunction "VDD_RTC6_N6") (pintype "bidirectional"))
    )
    (net (code "258") (name "unconnected-(U2E-VDD_RTC7-PadP9)") (class "Default")
      (node (ref "U2") (pin "P9") (pinfunction "VDD_RTC7_P9") (pintype "bidirectional"))
    )
    (net (code "259") (name "unconnected-(U2E-VDD_RTC8-PadP14)") (class "Default")
      (node (ref "U2") (pin "P14") (pinfunction "VDD_RTC8_P14") (pintype "bidirectional"))
    )
    (net (code "260") (name "unconnected-(U2E-VPP-PadM5)") (class "Default")
      (node (ref "U2") (pin "M5") (pinfunction "VPP_M5") (pintype "bidirectional"))
    )
    (net (code "261") (name "unconnected-(U2F-DGND2-PadA18)") (class "Default")
      (node (ref "U2") (pin "A18") (pinfunction "DGND2_A18") (pintype "bidirectional"))
    )
    (net (code "262") (name "unconnected-(U2F-DGND3-PadE19)") (class "Default")
      (node (ref "U2") (pin "E19") (pinfunction "DGND3_E19") (pintype "bidirectional"))
    )
    (net (code "263") (name "unconnected-(U2F-DGND4-PadE20)") (class "Default")
      (node (ref "U2") (pin "E20") (pinfunction "DGND4_E20") (pintype "bidirectional"))
    )
    (net (code "264") (name "unconnected-(U2F-DGND5-PadF8)") (class "Default")
      (node (ref "U2") (pin "F8") (pinfunction "DGND5_F8") (pintype "bidirectional"))
    )
    (net (code "265") (name "unconnected-(U2F-DGND6-PadF19)") (class "Default")
      (node (ref "U2") (pin "F19") (pinfunction "DGND6_F19") (pintype "bidirectional"))
    )
    (net (code "266") (name "unconnected-(U2F-DGND7-PadG8)") (class "Default")
      (node (ref "U2") (pin "G8") (pinfunction "DGND7_G8") (pintype "bidirectional"))
    )
    (net (code "267") (name "unconnected-(U2F-DGND8-PadG9)") (class "Default")
      (node (ref "U2") (pin "G9") (pinfunction "DGND8_G9") (pintype "bidirectional"))
    )
    (net (code "268") (name "unconnected-(U2F-DGND9-PadG11)") (class "Default")
      (node (ref "U2") (pin "G11") (pinfunction "DGND9_G11") (pintype "bidirectional"))
    )
    (net (code "269") (name "unconnected-(U2F-DGND10-PadG12)") (class "Default")
      (node (ref "U2") (pin "G12") (pinfunction "DGND10_G12") (pintype "bidirectional"))
    )
    (net (code "270") (name "unconnected-(U2F-DGND11-PadG19)") (class "Default")
      (node (ref "U2") (pin "G19") (pinfunction "DGND11_G19") (pintype "bidirectional"))
    )
    (net (code "271") (name "unconnected-(U2F-DGND12-PadH6)") (class "Default")
      (node (ref "U2") (pin "H6") (pinfunction "DGND12_H6") (pintype "bidirectional"))
    )
    (net (code "272") (name "unconnected-(U2F-DGND13-PadH7)") (class "Default")
      (node (ref "U2") (pin "H7") (pinfunction "DGND13_H7") (pintype "bidirectional"))
    )
    (net (code "273") (name "unconnected-(U2F-DGND14-PadH8)") (class "Default")
      (node (ref "U2") (pin "H8") (pinfunction "DGND14_H8") (pintype "bidirectional"))
    )
    (net (code "274") (name "unconnected-(U2F-DGND15-PadH9)") (class "Default")
      (node (ref "U2") (pin "H9") (pinfunction "DGND15_H9") (pintype "bidirectional"))
    )
    (net (code "275") (name "unconnected-(U2F-DGND16-PadH10)") (class "Default")
      (node (ref "U2") (pin "H10") (pinfunction "DGND16_H10") (pintype "bidirectional"))
    )
    (net (code "276") (name "unconnected-(U2F-DGND17-PadH12)") (class "Default")
      (node (ref "U2") (pin "H12") (pinfunction "DGND17_H12") (pintype "bidirectional"))
    )
    (net (code "277") (name "unconnected-(U2F-DGND18-PadH19)") (class "Default")
      (node (ref "U2") (pin "H19") (pinfunction "DGND18_H19") (pintype "bidirectional"))
    )
    (net (code "278") (name "unconnected-(U2F-DGND20-PadJ7)") (class "Default")
      (node (ref "U2") (pin "J7") (pinfunction "DGND20_J7") (pintype "bidirectional"))
    )
    (net (code "279") (name "unconnected-(U2F-DGND21-PadJ8)") (class "Default")
      (node (ref "U2") (pin "J8") (pinfunction "DGND21_J8") (pintype "bidirectional"))
    )
    (net (code "280") (name "unconnected-(U2F-DGND22-PadJ9)") (class "Default")
      (node (ref "U2") (pin "J9") (pinfunction "DGND22_J9") (pintype "bidirectional"))
    )
    (net (code "281") (name "unconnected-(U2F-DGND23-PadJ10)") (class "Default")
      (node (ref "U2") (pin "J10") (pinfunction "DGND23_J10") (pintype "bidirectional"))
    )
    (net (code "282") (name "unconnected-(U2F-DGND24-PadJ11)") (class "Default")
      (node (ref "U2") (pin "J11") (pinfunction "DGND24_J11") (pintype "bidirectional"))
    )
    (net (code "283") (name "unconnected-(U2F-DGND25-PadJ19)") (class "Default")
      (node (ref "U2") (pin "J19") (pinfunction "DGND25_J19") (pintype "bidirectional"))
    )
    (net (code "284") (name "unconnected-(U2F-DGND26-PadJ20)") (class "Default")
      (node (ref "U2") (pin "J20") (pinfunction "DGND26_J20") (pintype "bidirectional"))
    )
    (net (code "285") (name "unconnected-(U2F-DGND27-PadK7)") (class "Default")
      (node (ref "U2") (pin "K7") (pinfunction "DGND27_K7") (pintype "bidirectional"))
    )
    (net (code "286") (name "unconnected-(U2F-DGND28-PadK9)") (class "Default")
      (node (ref "U2") (pin "K9") (pinfunction "DGND28_K9") (pintype "bidirectional"))
    )
    (net (code "287") (name "unconnected-(U2F-DGND29-PadK10)") (class "Default")
      (node (ref "U2") (pin "K10") (pinfunction "DGND29_K10") (pintype "bidirectional"))
    )
    (net (code "288") (name "unconnected-(U2F-DGND30-PadK11)") (class "Default")
      (node (ref "U2") (pin "K11") (pinfunction "DGND30_K11") (pintype "bidirectional"))
    )
    (net (code "289") (name "unconnected-(U2F-DGND31-PadK19)") (class "Default")
      (node (ref "U2") (pin "K19") (pinfunction "DGND31_K19") (pintype "bidirectional"))
    )
    (net (code "290") (name "unconnected-(U2F-DGND32-PadL10)") (class "Default")
      (node (ref "U2") (pin "L10") (pinfunction "DGND32_L10") (pintype "bidirectional"))
    )
    (net (code "291") (name "unconnected-(U2F-DGND33-PadL11)") (class "Default")
      (node (ref "U2") (pin "L11") (pinfunction "DGND33_L11") (pintype "bidirectional"))
    )
    (net (code "292") (name "unconnected-(U2F-DGND34-PadL12)") (class "Default")
      (node (ref "U2") (pin "L12") (pinfunction "DGND34_L12") (pintype "bidirectional"))
    )
    (net (code "293") (name "unconnected-(U2F-DGND35-PadL13)") (class "Default")
      (node (ref "U2") (pin "L13") (pinfunction "DGND35_L13") (pintype "bidirectional"))
    )
    (net (code "294") (name "unconnected-(U2F-DGND38-PadM6)") (class "Default")
      (node (ref "U2") (pin "M6") (pinfunction "DGND38_M6") (pintype "bidirectional"))
    )
    (net (code "295") (name "unconnected-(U2F-DGND39-PadM7)") (class "Default")
      (node (ref "U2") (pin "M7") (pinfunction "DGND39_M7") (pintype "bidirectional"))
    )
    (net (code "296") (name "unconnected-(U2F-DGND40-PadM8)") (class "Default")
      (node (ref "U2") (pin "M8") (pinfunction "DGND40_M8") (pintype "bidirectional"))
    )
    (net (code "297") (name "unconnected-(U2F-DGND41-PadM9)") (class "Default")
      (node (ref "U2") (pin "M9") (pinfunction "DGND41_M9") (pintype "bidirectional"))
    )
    (net (code "298") (name "unconnected-(U2F-DGND43-PadM12)") (class "Default")
      (node (ref "U2") (pin "M12") (pinfunction "DGND43_M12") (pintype "bidirectional"))
    )
    (net (code "299") (name "unconnected-(U2F-DGND44-PadM14)") (class "Default")
      (node (ref "U2") (pin "M14") (pinfunction "DGND44_M14") (pintype "bidirectional"))
    )
    (net (code "300") (name "unconnected-(U2F-DGND47-PadN10)") (class "Default")
      (node (ref "U2") (pin "N10") (pinfunction "DGND47_N10") (pintype "bidirectional"))
    )
    (net (code "301") (name "unconnected-(U2F-DGND48-PadN11)") (class "Default")
      (node (ref "U2") (pin "N11") (pinfunction "DGND48_N11") (pintype "bidirectional"))
    )
    (net (code "302") (name "unconnected-(U2F-DGND49-PadN14)") (class "Default")
      (node (ref "U2") (pin "N14") (pinfunction "DGND49_N14") (pintype "bidirectional"))
    )
    (net (code "303") (name "unconnected-(U2F-DGND50-PadN19)") (class "Default")
      (node (ref "U2") (pin "N19") (pinfunction "DGND50_N19") (pintype "bidirectional"))
    )
    (net (code "304") (name "unconnected-(U2F-DGND51-PadN20)") (class "Default")
      (node (ref "U2") (pin "N20") (pinfunction "DGND51_N20") (pintype "bidirectional"))
    )
    (net (code "305") (name "unconnected-(U2F-DGND52-PadP19)") (class "Default")
      (node (ref "U2") (pin "P19") (pinfunction "DGND52_P19") (pintype "bidirectional"))
    )
    (net (code "306") (name "unconnected-(U2F-DGND53-PadP20)") (class "Default")
      (node (ref "U2") (pin "P20") (pinfunction "DGND53_P20") (pintype "bidirectional"))
    )
    (net (code "307") (name "unconnected-(U2F-DGND54-PadR19)") (class "Default")
      (node (ref "U2") (pin "R19") (pinfunction "DGND54_R19") (pintype "bidirectional"))
    )
    (net (code "308") (name "unconnected-(U2F-DGND55-PadR20)") (class "Default")
      (node (ref "U2") (pin "R20") (pinfunction "DGND55_R20") (pintype "bidirectional"))
    )
    (net (code "309") (name "unconnected-(U2F-DGND56-PadT19)") (class "Default")
      (node (ref "U2") (pin "T19") (pinfunction "DGND56_T19") (pintype "bidirectional"))
    )
    (net (code "310") (name "unconnected-(U2F-DGND57-PadT20)") (class "Default")
      (node (ref "U2") (pin "T20") (pinfunction "DGND57_T20") (pintype "bidirectional"))
    )
    (net (code "311") (name "unconnected-(U2F-DGND58-PadU19)") (class "Default")
      (node (ref "U2") (pin "U19") (pinfunction "DGND58_U19") (pintype "bidirectional"))
    )
    (net (code "312") (name "unconnected-(U2F-DGND60-PadV18)") (class "Default")
      (node (ref "U2") (pin "V18") (pinfunction "DGND60_V18") (pintype "bidirectional"))
    )
    (net (code "313") (name "unconnected-(U2F-DGND63-PadW3)") (class "Default")
      (node (ref "U2") (pin "W3") (pinfunction "DGND63_W3") (pintype "bidirectional"))
    )
    (net (code "314") (name "unconnected-(U2F-DGND65-PadW5)") (class "Default")
      (node (ref "U2") (pin "W5") (pinfunction "DGND65_W5") (pintype "bidirectional"))
    )
    (net (code "315") (name "unconnected-(U2F-DGND66-PadW6)") (class "Default")
      (node (ref "U2") (pin "W6") (pinfunction "DGND66_W6") (pintype "bidirectional"))
    )
    (net (code "316") (name "unconnected-(U2F-DGND67-PadW7)") (class "Default")
      (node (ref "U2") (pin "W7") (pinfunction "DGND67_W7") (pintype "bidirectional"))
    )
    (net (code "317") (name "unconnected-(U2F-DGND68-PadW8)") (class "Default")
      (node (ref "U2") (pin "W8") (pinfunction "DGND68_W8") (pintype "bidirectional"))
    )
    (net (code "318") (name "unconnected-(U2F-DGND69-PadW9)") (class "Default")
      (node (ref "U2") (pin "W9") (pinfunction "DGND69_W9") (pintype "bidirectional"))
    )
    (net (code "319") (name "unconnected-(U2F-DGND70-PadW10)") (class "Default")
      (node (ref "U2") (pin "W10") (pinfunction "DGND70_W10") (pintype "bidirectional"))
    )
    (net (code "320") (name "unconnected-(U2F-DGND72-PadW12)") (class "Default")
      (node (ref "U2") (pin "W12") (pinfunction "DGND72_W12") (pintype "bidirectional"))
    )
    (net (code "321") (name "unconnected-(U2F-DGND73-PadW13)") (class "Default")
      (node (ref "U2") (pin "W13") (pinfunction "DGND73_W13") (pintype "bidirectional"))
    )
    (net (code "322") (name "unconnected-(U2F-DGND74-PadW14)") (class "Default")
      (node (ref "U2") (pin "W14") (pinfunction "DGND74_W14") (pintype "bidirectional"))
    )
    (net (code "323") (name "unconnected-(U2F-DGND75-PadW15)") (class "Default")
      (node (ref "U2") (pin "W15") (pinfunction "DGND75_W15") (pintype "bidirectional"))
    )
    (net (code "324") (name "unconnected-(U2F-DGND76-PadW16)") (class "Default")
      (node (ref "U2") (pin "W16") (pinfunction "DGND76_W16") (pintype "bidirectional"))
    )
    (net (code "325") (name "unconnected-(U2F-DGND77-PadW17)") (class "Default")
      (node (ref "U2") (pin "W17") (pinfunction "DGND77_W17") (pintype "bidirectional"))
    )
    (net (code "326") (name "unconnected-(U2F-DGND78-PadW18)") (class "Default")
      (node (ref "U2") (pin "W18") (pinfunction "DGND78_W18") (pintype "bidirectional"))
    )
    (net (code "327") (name "unconnected-(U2F-DGND79-PadW19)") (class "Default")
      (node (ref "U2") (pin "W19") (pinfunction "DGND79_W19") (pintype "bidirectional"))
    )
    (net (code "328") (name "unconnected-(U2F-DGND82-PadY7)") (class "Default")
      (node (ref "U2") (pin "Y7") (pinfunction "DGND82_Y7") (pintype "bidirectional"))
    )
    (net (code "329") (name "unconnected-(U2F-DGND83-PadY10)") (class "Default")
      (node (ref "U2") (pin "Y10") (pinfunction "DGND83_Y10") (pintype "bidirectional"))
    )
    (net (code "330") (name "unconnected-(U2F-DGND84-PadY12)") (class "Default")
      (node (ref "U2") (pin "Y12") (pinfunction "DGND84_Y12") (pintype "bidirectional"))
    )
    (net (code "331") (name "unconnected-(U2F-DGND85-PadY15)") (class "Default")
      (node (ref "U2") (pin "Y15") (pinfunction "DGND85_Y15") (pintype "bidirectional"))
    )
    (net (code "332") (name "unconnected-(U3-NC-Pad1)") (class "Default")
      (node (ref "U3") (pin "1") (pinfunction "NC_1") (pintype "passive"))
    )
  )
)
